# elements_v02.net
KiCad netlist of a schematic drawn in EAGLE
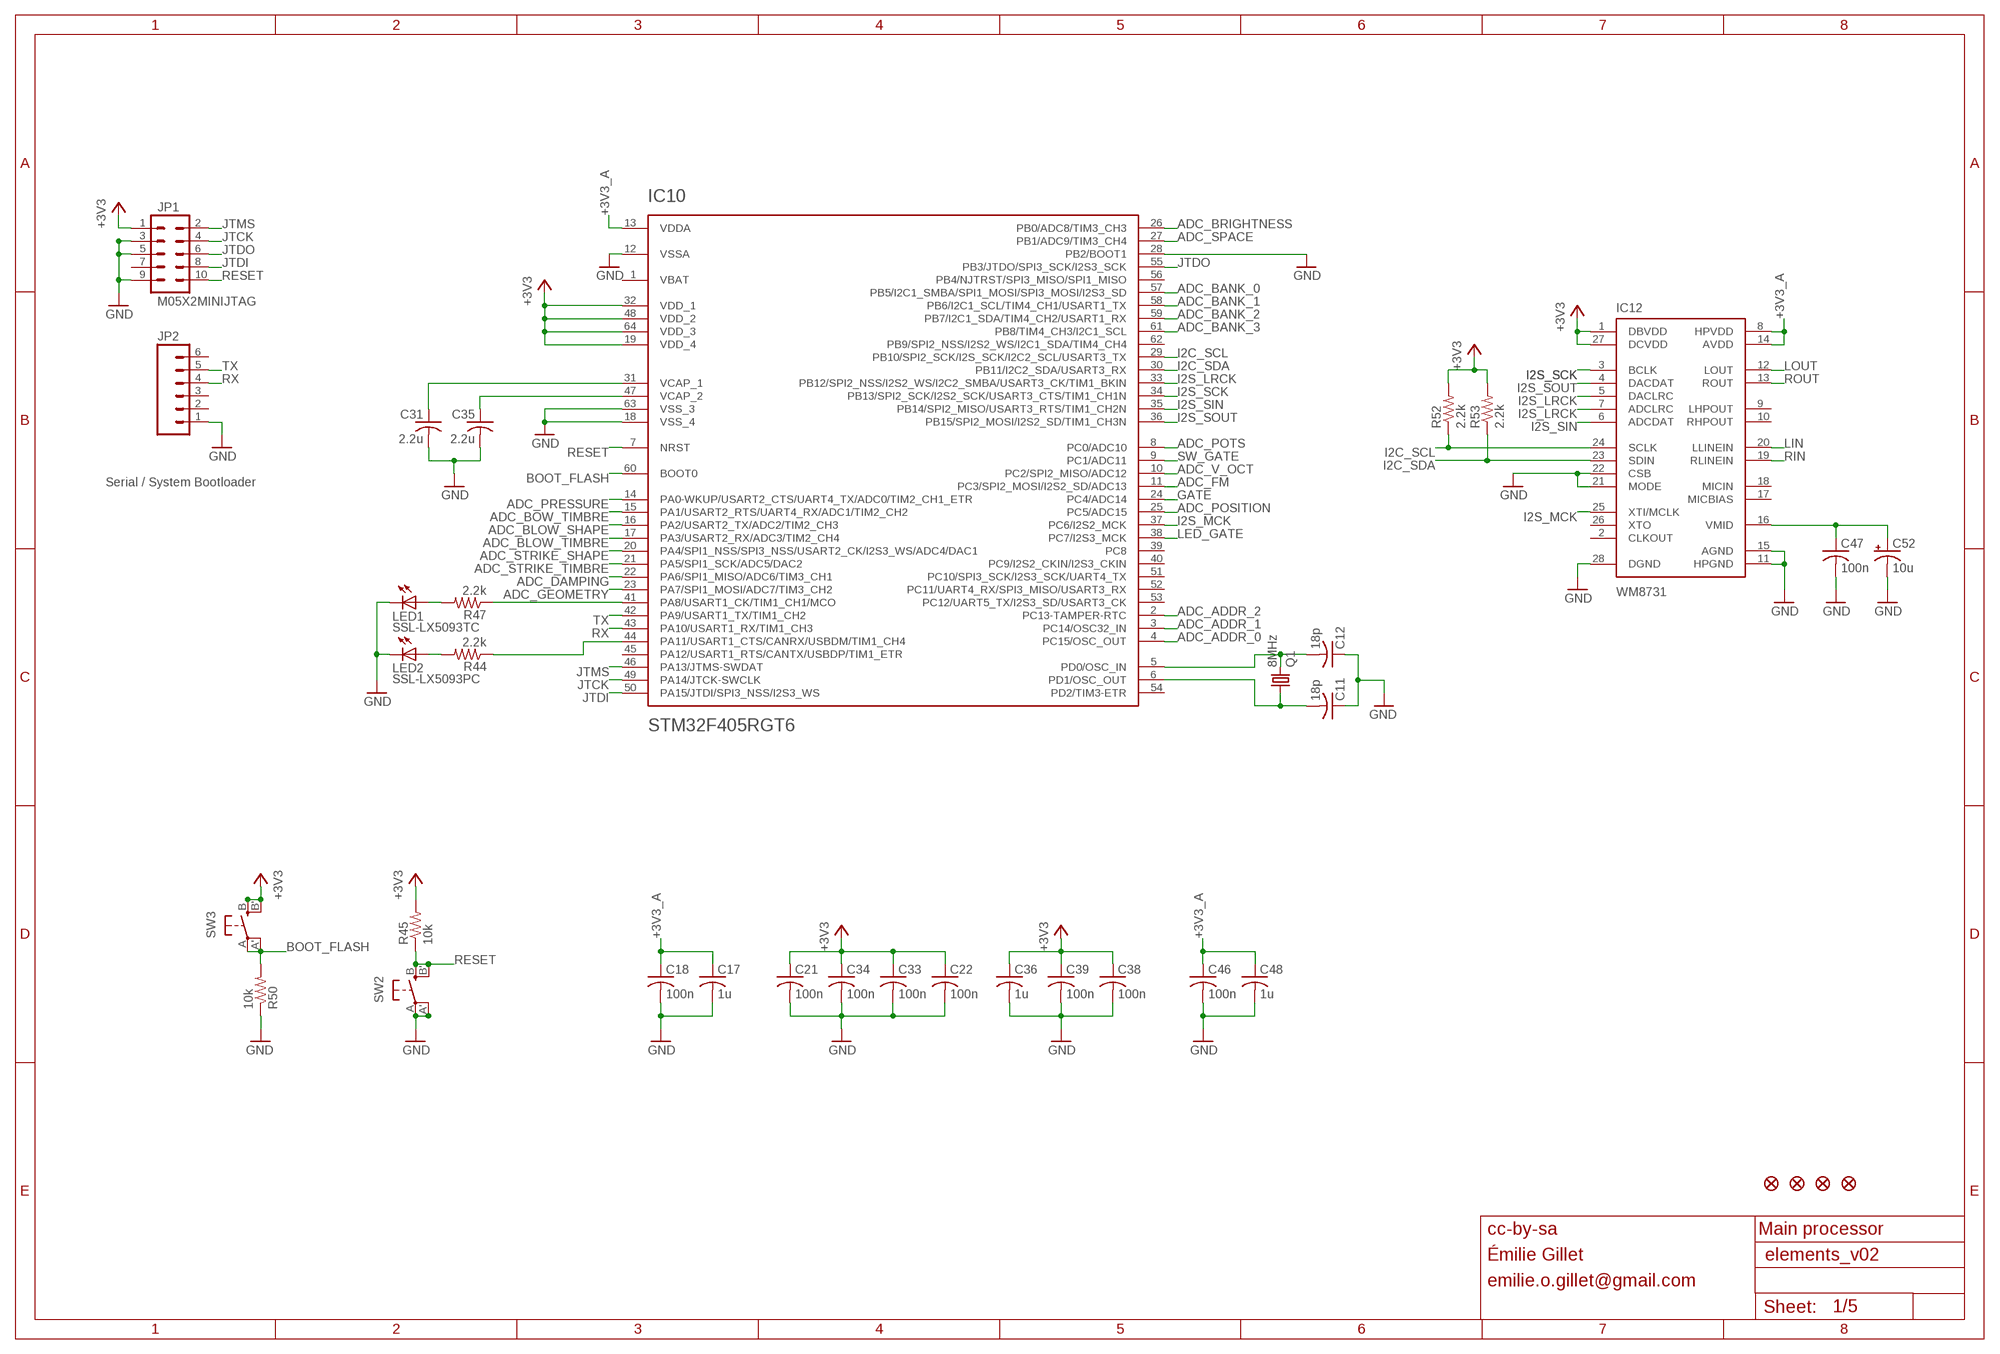
[diagram p0: schematic, sheet 1]
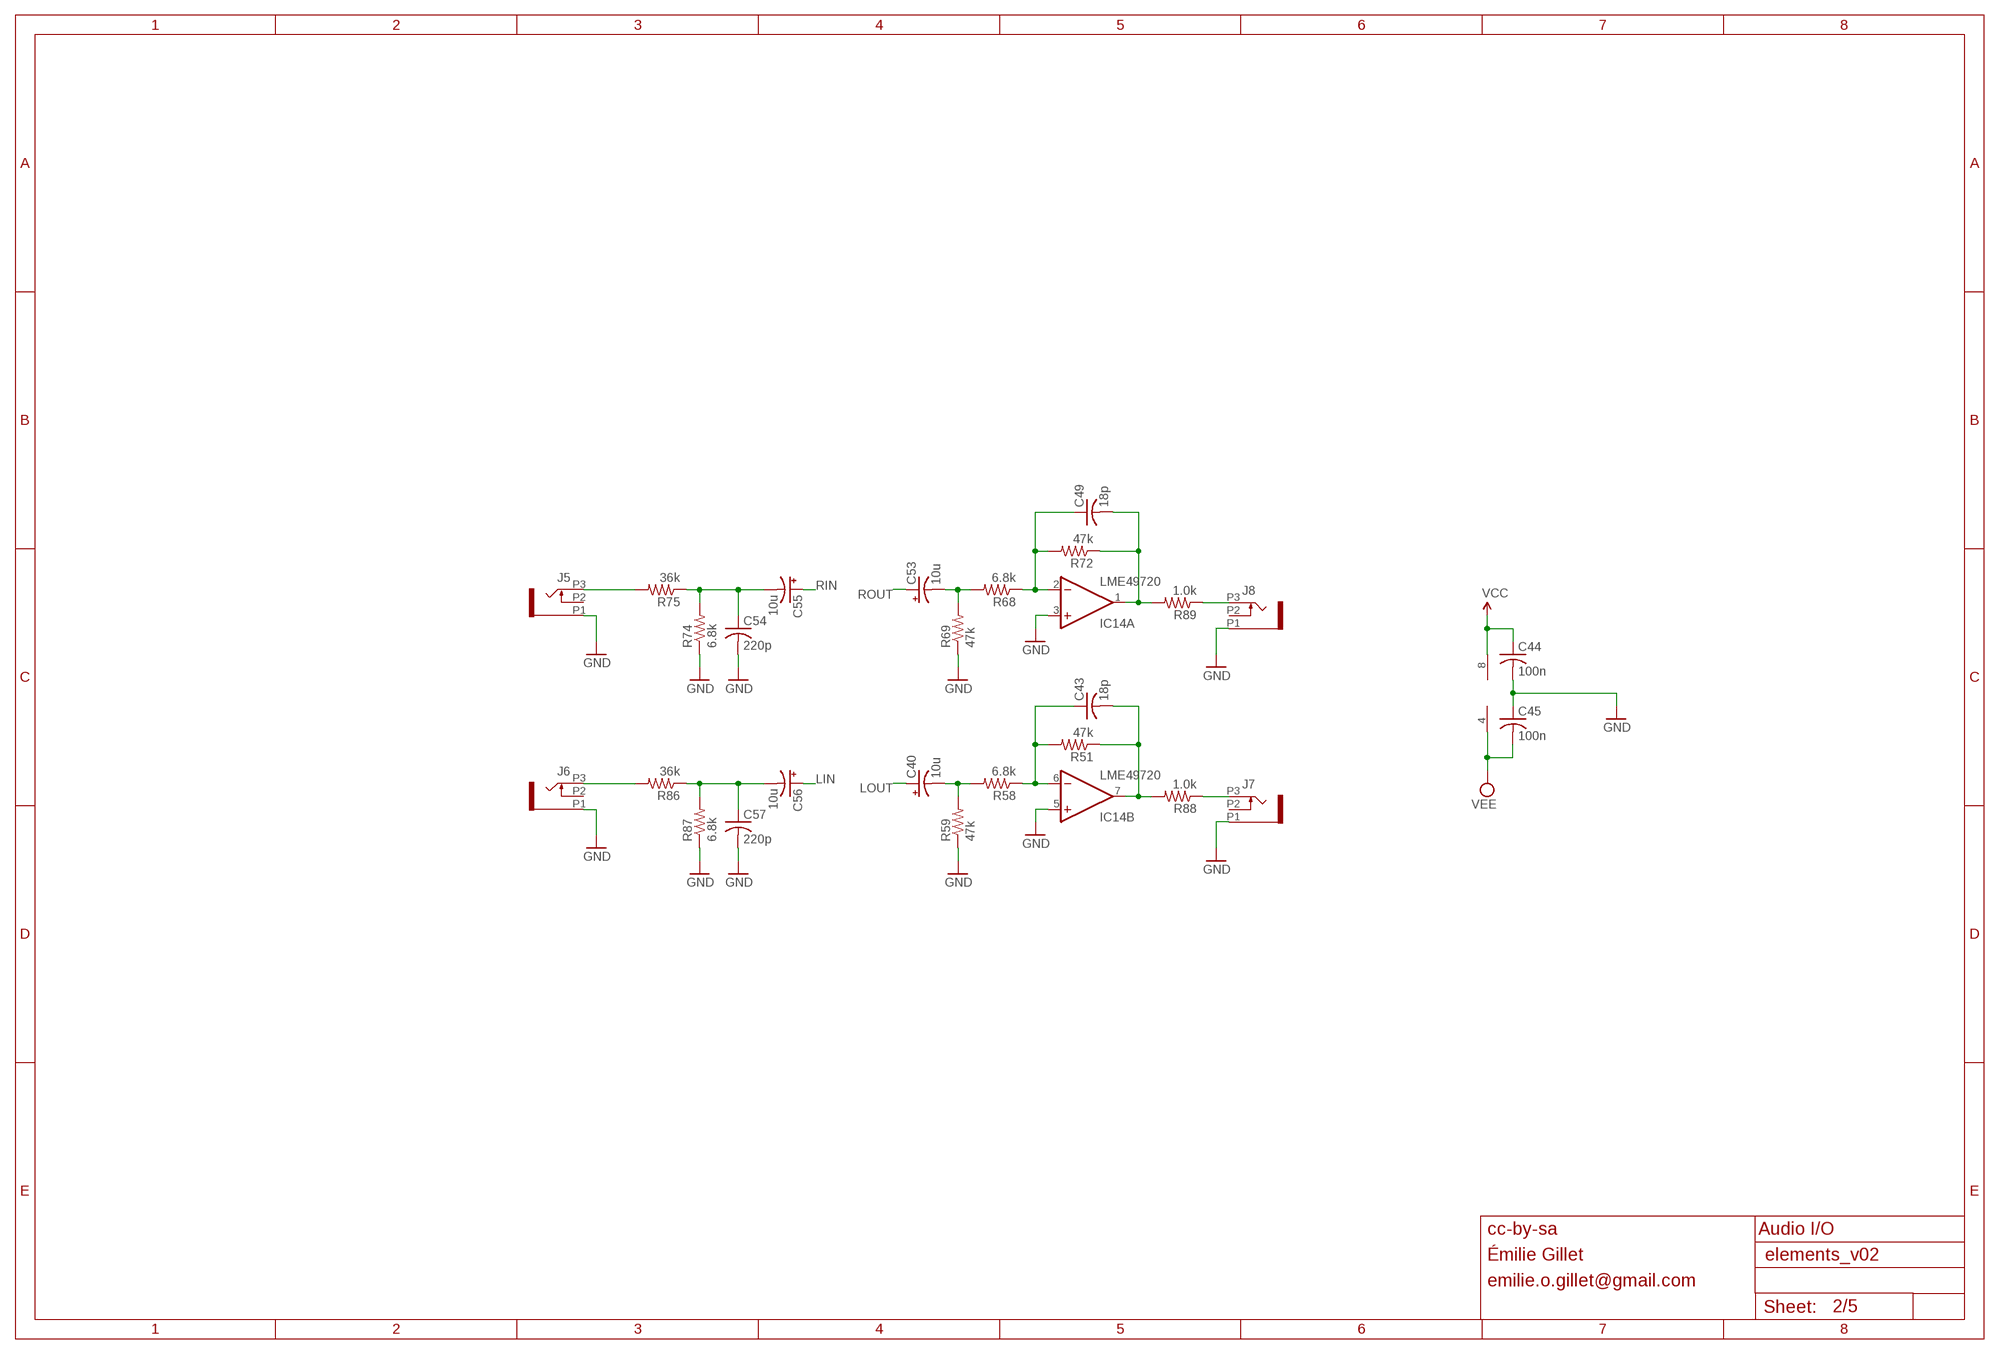
[diagram p1: schematic, sheet 2]
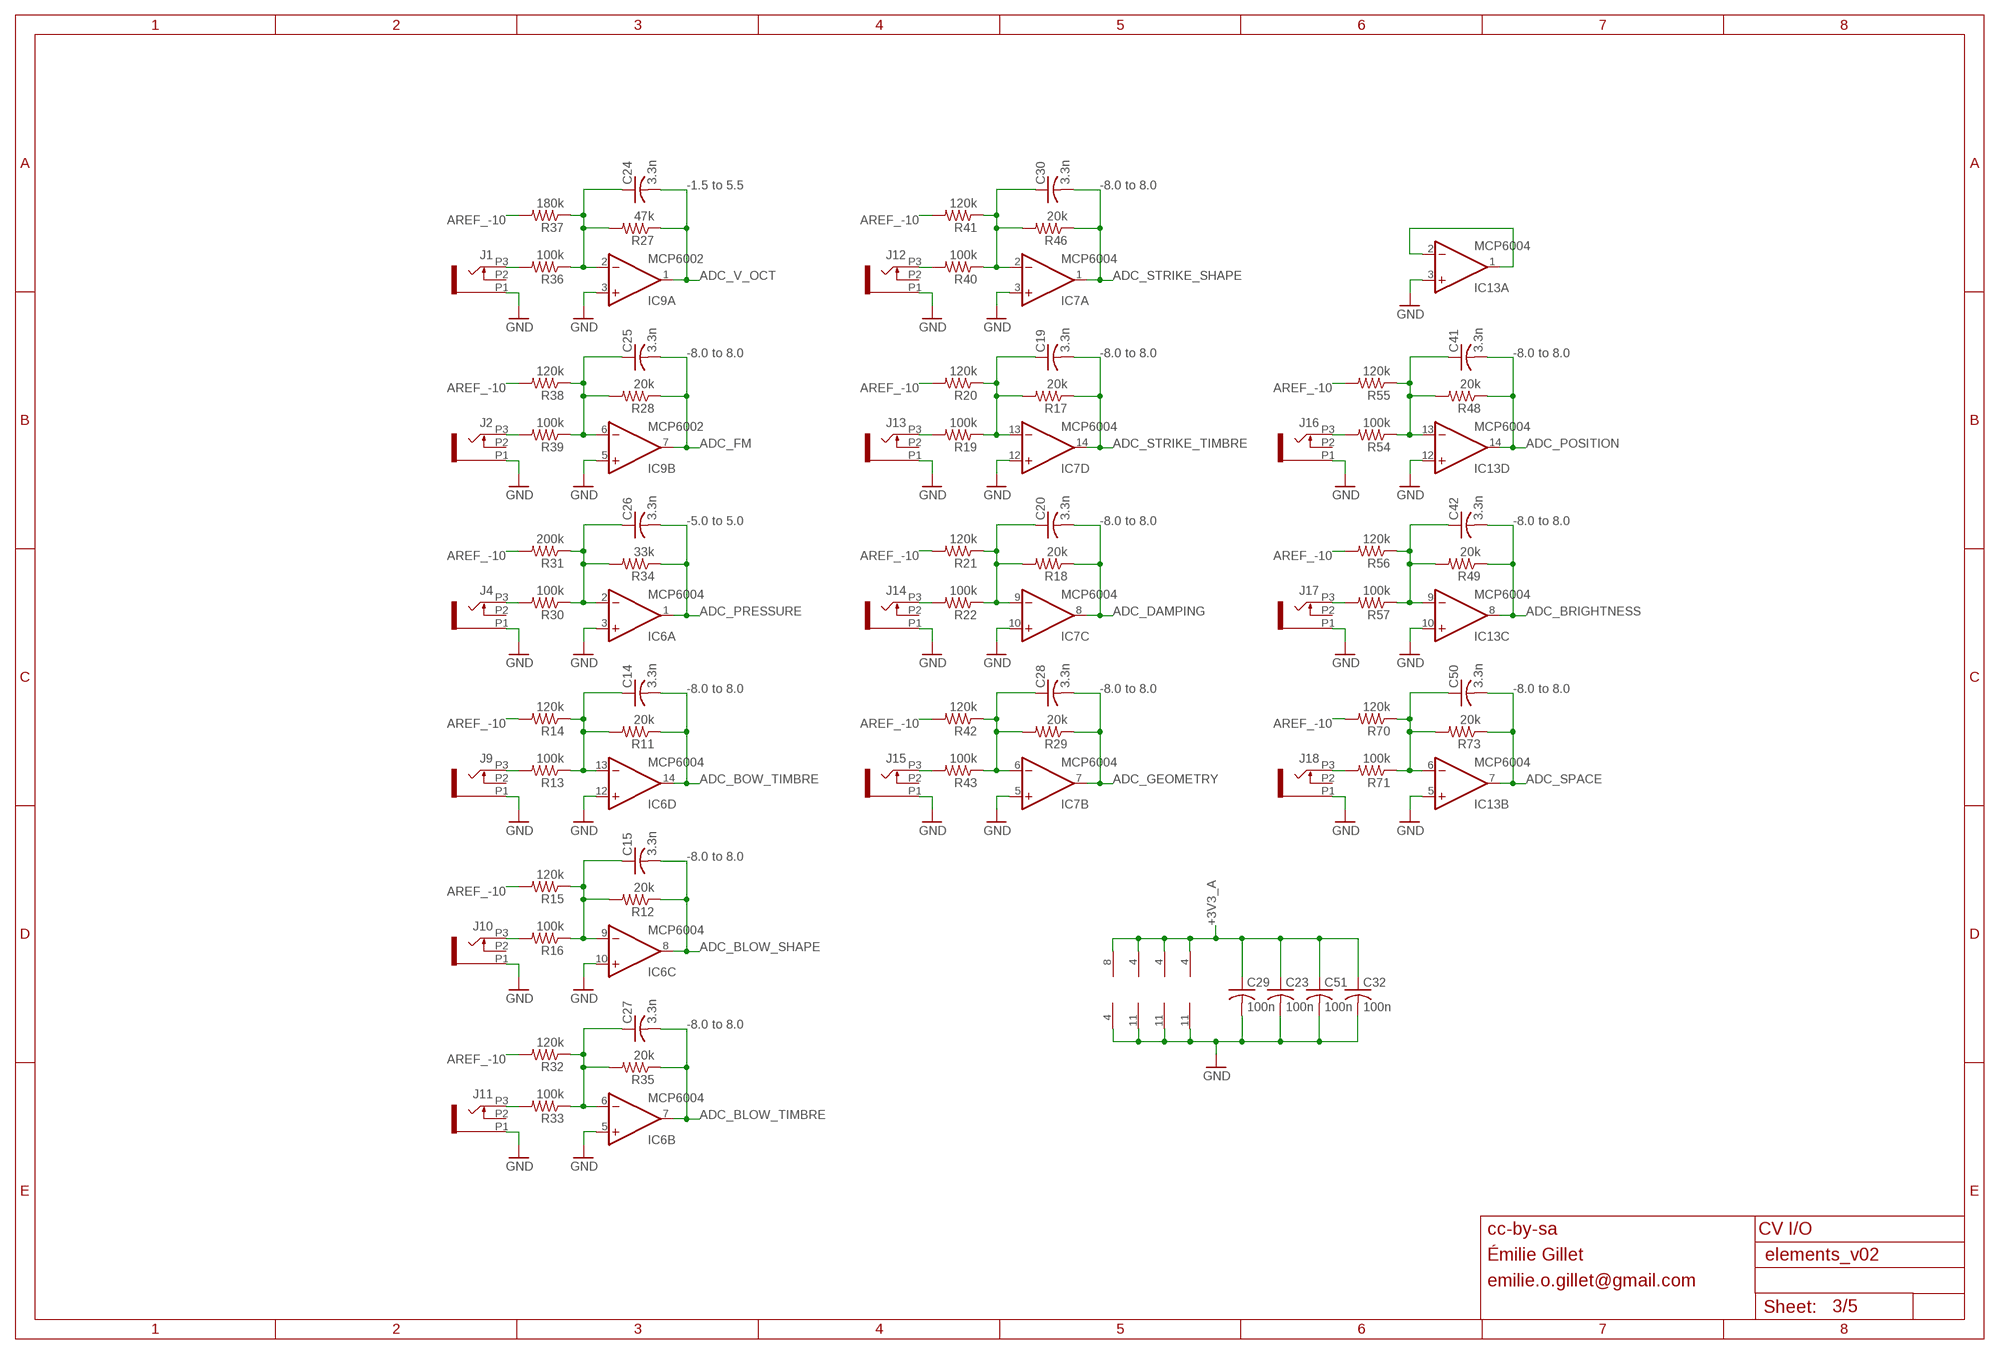
[diagram p2: schematic, sheet 3]
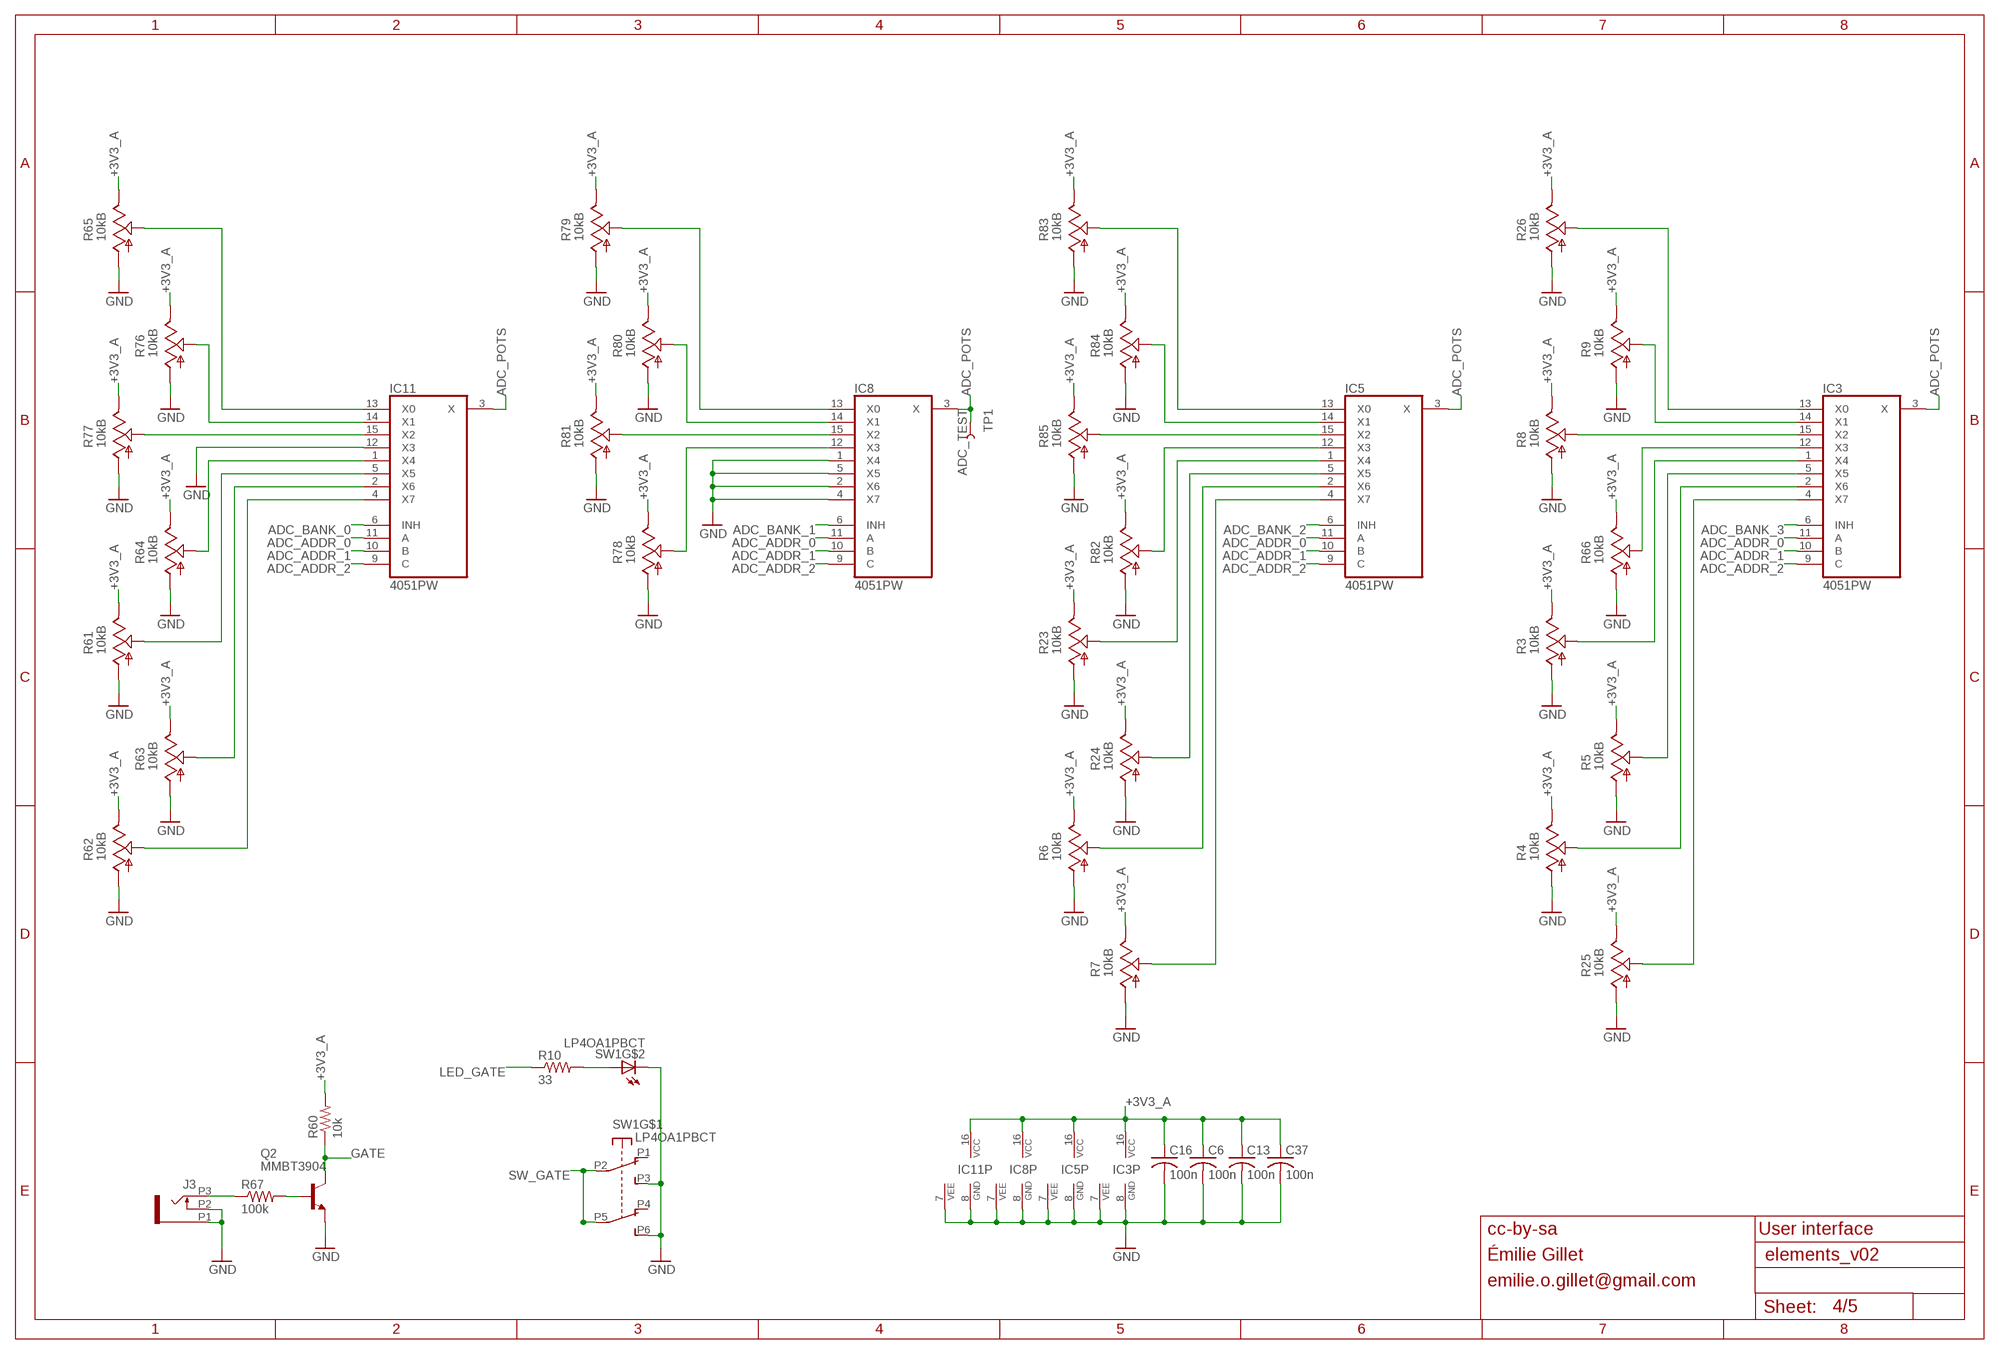
[diagram p3: schematic, sheet 4]
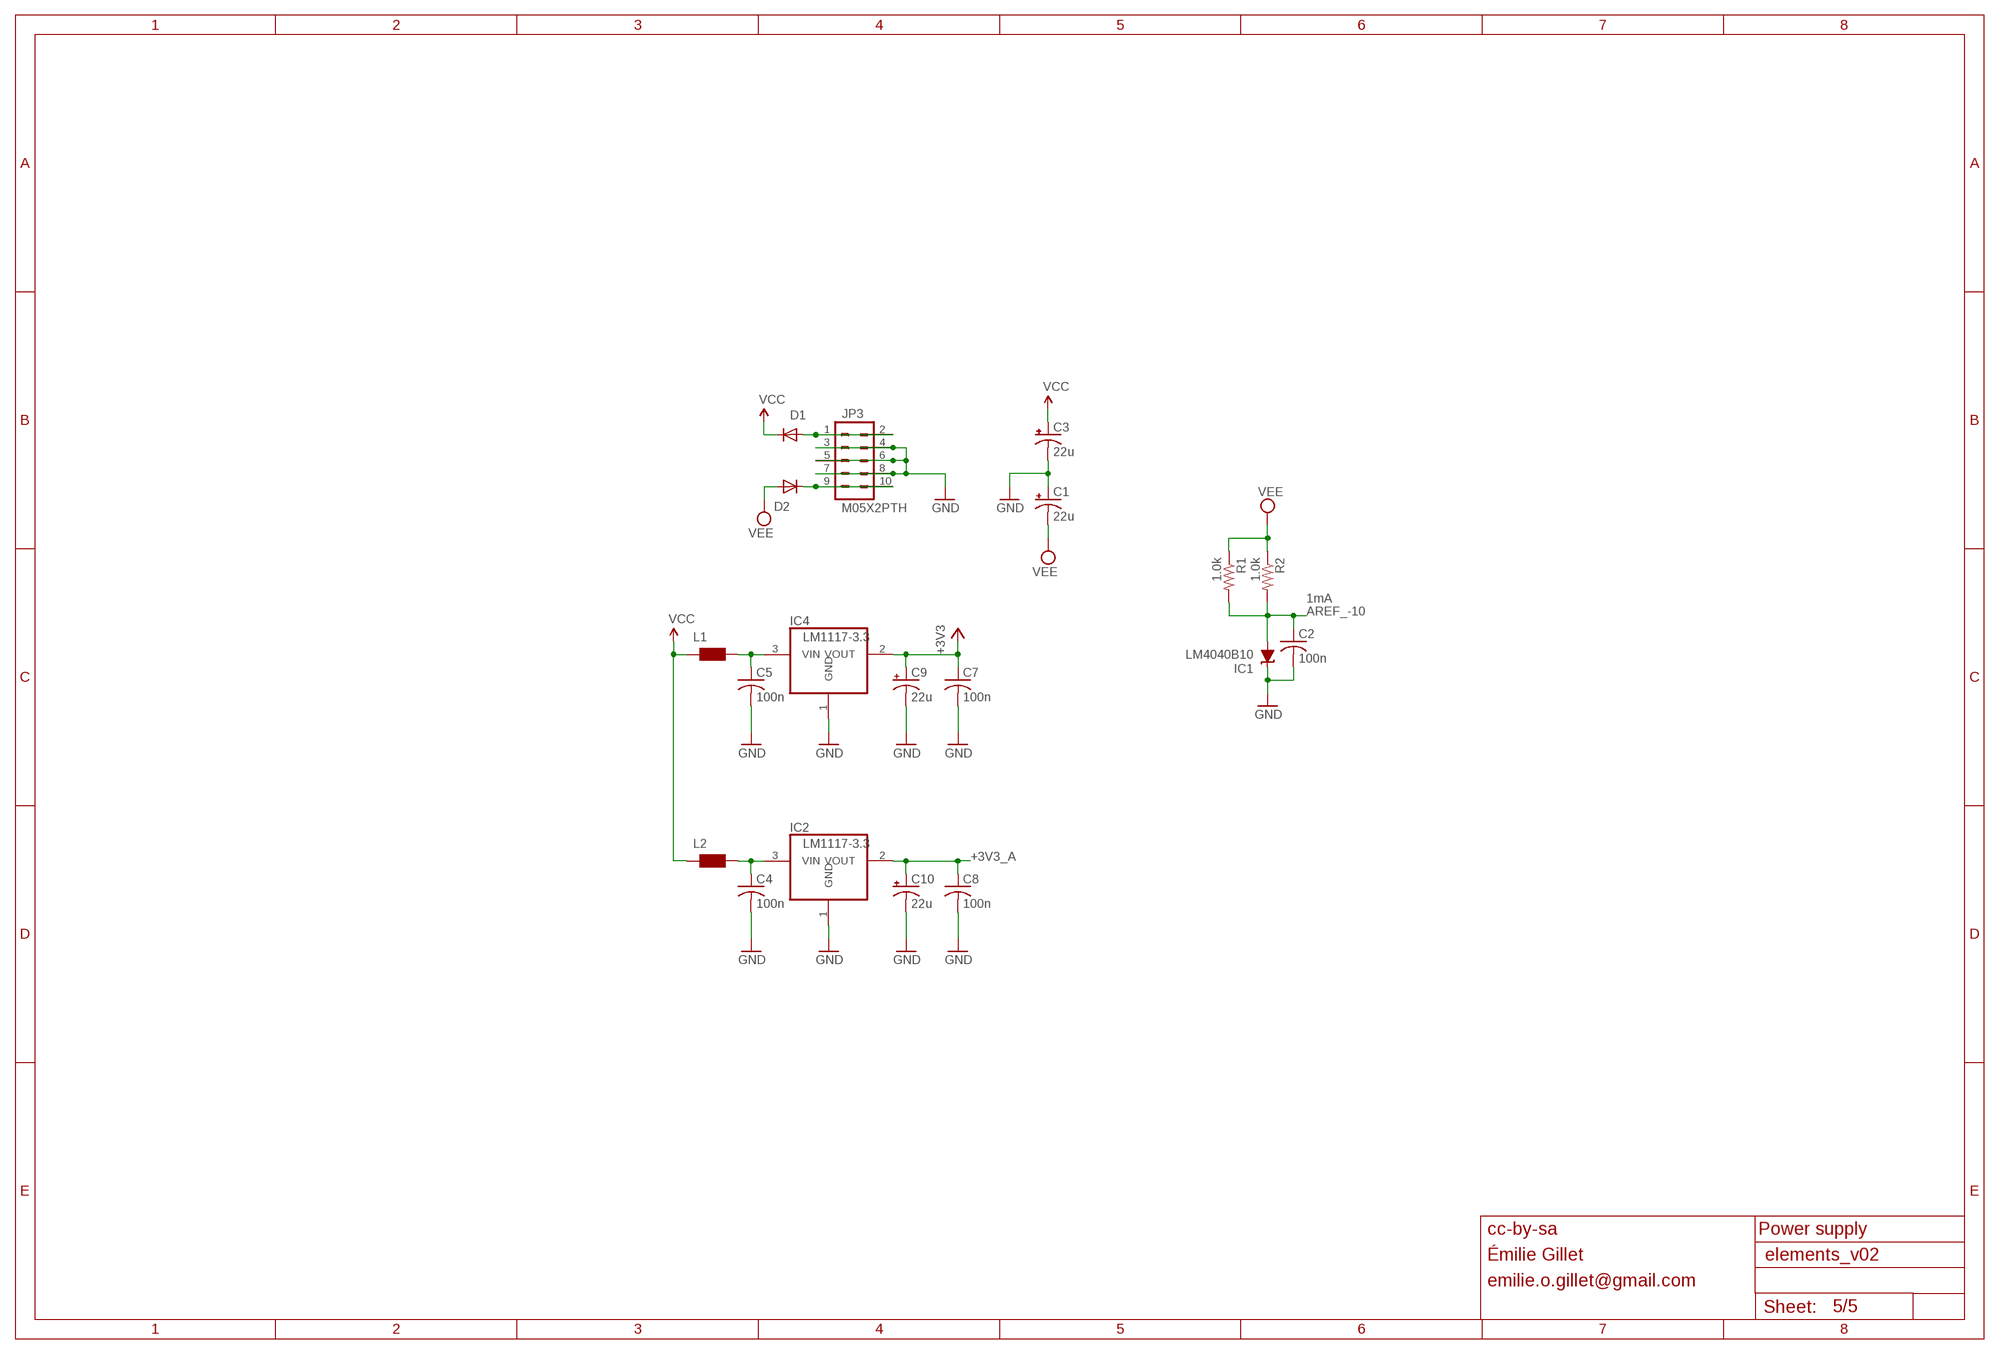
[diagram p4: schematic, sheet 5]

(export (version "E")
  (design (tool "Eeschema 10.0.6"))
  (components
    (comp (ref "C14")
      (value "3.3n")
      (footprint "eagle-import:C0603")
      (libsource (lib "eagle-import") (part "C-USC0603"))
    )
    (comp (ref "C15")
      (value "3.3n")
      (footprint "eagle-import:C0603")
      (libsource (lib "eagle-import") (part "C-USC0603"))
    )
    (comp (ref "C19")
      (value "3.3n")
      (footprint "eagle-import:C0603")
      (libsource (lib "eagle-import") (part "C-USC0603"))
    )
    (comp (ref "C20")
      (value "3.3n")
      (footprint "eagle-import:C0603")
      (libsource (lib "eagle-import") (part "C-USC0603"))
    )
    (comp (ref "C23")
      (value "100n")
      (footprint "eagle-import:C0603")
      (libsource (lib "eagle-import") (part "C-USC0603"))
    )
    (comp (ref "C24")
      (value "3.3n")
      (footprint "eagle-import:C0603")
      (libsource (lib "eagle-import") (part "C-USC0603"))
    )
    (comp (ref "C25")
      (value "3.3n")
      (footprint "eagle-import:C0603")
      (libsource (lib "eagle-import") (part "C-USC0603"))
    )
    (comp (ref "C26")
      (value "3.3n")
      (footprint "eagle-import:C0603")
      (libsource (lib "eagle-import") (part "C-USC0603"))
    )
    (comp (ref "C27")
      (value "3.3n")
      (footprint "eagle-import:C0603")
      (libsource (lib "eagle-import") (part "C-USC0603"))
    )
    (comp (ref "C28")
      (value "3.3n")
      (footprint "eagle-import:C0603")
      (libsource (lib "eagle-import") (part "C-USC0603"))
    )
    (comp (ref "C29")
      (value "100n")
      (footprint "eagle-import:C0603")
      (libsource (lib "eagle-import") (part "C-USC0603"))
    )
    (comp (ref "C30")
      (value "3.3n")
      (footprint "eagle-import:C0603")
      (libsource (lib "eagle-import") (part "C-USC0603"))
    )
    (comp (ref "C32")
      (value "100n")
      (footprint "eagle-import:C0603")
      (libsource (lib "eagle-import") (part "C-USC0603"))
    )
    (comp (ref "C41")
      (value "3.3n")
      (footprint "eagle-import:C0603")
      (libsource (lib "eagle-import") (part "C-USC0603"))
    )
    (comp (ref "C42")
      (value "3.3n")
      (footprint "eagle-import:C0603")
      (libsource (lib "eagle-import") (part "C-USC0603"))
    )
    (comp (ref "C50")
      (value "3.3n")
      (footprint "eagle-import:C0603")
      (libsource (lib "eagle-import") (part "C-USC0603"))
    )
    (comp (ref "C51")
      (value "100n")
      (footprint "eagle-import:C0603")
      (libsource (lib "eagle-import") (part "C-USC0603"))
    )
    (comp (ref "IC6")
      (value "MCP6004")
      (footprint "eagle-import:SO14")
      (libsource (lib "eagle-import") (part "TL074D"))
    )
    (comp (ref "IC7")
      (value "MCP6004")
      (footprint "eagle-import:SO14")
      (libsource (lib "eagle-import") (part "TL074D"))
    )
    (comp (ref "IC9")
      (value "MCP6002")
      (footprint "eagle-import:SO08")
      (libsource (lib "eagle-import") (part "TL072D"))
    )
    (comp (ref "IC13")
      (value "MCP6004")
      (footprint "eagle-import:SO14")
      (libsource (lib "eagle-import") (part "TL074D"))
    )
    (comp (ref "J1")
      (value "PJ301_THONKICONN6")
      (footprint "eagle-import:WQP_PJ_301M6")
      (libsource (lib "eagle-import") (part "PJ301_THONKICONN6"))
    )
    (comp (ref "J2")
      (value "PJ301_THONKICONN6")
      (footprint "eagle-import:WQP_PJ_301M6")
      (libsource (lib "eagle-import") (part "PJ301_THONKICONN6"))
    )
    (comp (ref "J4")
      (value "PJ301_THONKICONN6")
      (footprint "eagle-import:WQP_PJ_301M6")
      (libsource (lib "eagle-import") (part "PJ301_THONKICONN6"))
    )
    (comp (ref "J9")
      (value "PJ301_THONKICONN6")
      (footprint "eagle-import:WQP_PJ_301M6")
      (libsource (lib "eagle-import") (part "PJ301_THONKICONN6"))
    )
    (comp (ref "J10")
      (value "PJ301_THONKICONN6")
      (footprint "eagle-import:WQP_PJ_301M6")
      (libsource (lib "eagle-import") (part "PJ301_THONKICONN6"))
    )
    (comp (ref "J11")
      (value "PJ301_THONKICONN6")
      (footprint "eagle-import:WQP_PJ_301M6")
      (libsource (lib "eagle-import") (part "PJ301_THONKICONN6"))
    )
    (comp (ref "J12")
      (value "PJ301_THONKICONN6")
      (footprint "eagle-import:WQP_PJ_301M6")
      (libsource (lib "eagle-import") (part "PJ301_THONKICONN6"))
    )
    (comp (ref "J13")
      (value "PJ301_THONKICONN6")
      (footprint "eagle-import:WQP_PJ_301M6")
      (libsource (lib "eagle-import") (part "PJ301_THONKICONN6"))
    )
    (comp (ref "J14")
      (value "PJ301_THONKICONN6")
      (footprint "eagle-import:WQP_PJ_301M6")
      (libsource (lib "eagle-import") (part "PJ301_THONKICONN6"))
    )
    (comp (ref "J15")
      (value "PJ301_THONKICONN6")
      (footprint "eagle-import:WQP_PJ_301M6")
      (libsource (lib "eagle-import") (part "PJ301_THONKICONN6"))
    )
    (comp (ref "J16")
      (value "PJ301_THONKICONN6")
      (footprint "eagle-import:WQP_PJ_301M6")
      (libsource (lib "eagle-import") (part "PJ301_THONKICONN6"))
    )
    (comp (ref "J17")
      (value "PJ301_THONKICONN6")
      (footprint "eagle-import:WQP_PJ_301M6")
      (libsource (lib "eagle-import") (part "PJ301_THONKICONN6"))
    )
    (comp (ref "J18")
      (value "PJ301_THONKICONN6")
      (footprint "eagle-import:WQP_PJ_301M6")
      (libsource (lib "eagle-import") (part "PJ301_THONKICONN6"))
    )
    (comp (ref "R11")
      (value "20k")
      (footprint "eagle-import:R0603")
      (libsource (lib "eagle-import") (part "R-US_R0603"))
    )
    (comp (ref "R12")
      (value "20k")
      (footprint "eagle-import:R0603")
      (libsource (lib "eagle-import") (part "R-US_R0603"))
    )
    (comp (ref "R13")
      (value "100k")
      (footprint "eagle-import:R0603")
      (libsource (lib "eagle-import") (part "R-US_R0603"))
    )
    (comp (ref "R14")
      (value "120k")
      (footprint "eagle-import:R0603")
      (libsource (lib "eagle-import") (part "R-US_R0603"))
    )
    (comp (ref "R15")
      (value "120k")
      (footprint "eagle-import:R0603")
      (libsource (lib "eagle-import") (part "R-US_R0603"))
    )
    (comp (ref "R16")
      (value "100k")
      (footprint "eagle-import:R0603")
      (libsource (lib "eagle-import") (part "R-US_R0603"))
    )
    (comp (ref "R17")
      (value "20k")
      (footprint "eagle-import:R0603")
      (libsource (lib "eagle-import") (part "R-US_R0603"))
    )
    (comp (ref "R18")
      (value "20k")
      (footprint "eagle-import:R0603")
      (libsource (lib "eagle-import") (part "R-US_R0603"))
    )
    (comp (ref "R19")
      (value "100k")
      (footprint "eagle-import:R0603")
      (libsource (lib "eagle-import") (part "R-US_R0603"))
    )
    (comp (ref "R20")
      (value "120k")
      (footprint "eagle-import:R0603")
      (libsource (lib "eagle-import") (part "R-US_R0603"))
    )
    (comp (ref "R21")
      (value "120k")
      (footprint "eagle-import:R0603")
      (libsource (lib "eagle-import") (part "R-US_R0603"))
    )
    (comp (ref "R22")
      (value "100k")
      (footprint "eagle-import:R0603")
      (libsource (lib "eagle-import") (part "R-US_R0603"))
    )
    (comp (ref "R27")
      (value "47k")
      (footprint "eagle-import:R0603")
      (libsource (lib "eagle-import") (part "R-US_R0603"))
    )
    (comp (ref "R28")
      (value "20k")
      (footprint "eagle-import:R0603")
      (libsource (lib "eagle-import") (part "R-US_R0603"))
    )
    (comp (ref "R29")
      (value "20k")
      (footprint "eagle-import:R0603")
      (libsource (lib "eagle-import") (part "R-US_R0603"))
    )
    (comp (ref "R30")
      (value "100k")
      (footprint "eagle-import:R0603")
      (libsource (lib "eagle-import") (part "R-US_R0603"))
    )
    (comp (ref "R31")
      (value "200k")
      (footprint "eagle-import:R0603")
      (libsource (lib "eagle-import") (part "R-US_R0603"))
    )
    (comp (ref "R32")
      (value "120k")
      (footprint "eagle-import:R0603")
      (libsource (lib "eagle-import") (part "R-US_R0603"))
    )
    (comp (ref "R33")
      (value "100k")
      (footprint "eagle-import:R0603")
      (libsource (lib "eagle-import") (part "R-US_R0603"))
    )
    (comp (ref "R34")
      (value "33k")
      (footprint "eagle-import:R0603")
      (libsource (lib "eagle-import") (part "R-US_R0603"))
    )
    (comp (ref "R35")
      (value "20k")
      (footprint "eagle-import:R0603")
      (libsource (lib "eagle-import") (part "R-US_R0603"))
    )
    (comp (ref "R36")
      (value "100k")
      (footprint "eagle-import:R0603")
      (libsource (lib "eagle-import") (part "R-US_R0603"))
    )
    (comp (ref "R37")
      (value "180k")
      (footprint "eagle-import:R0603")
      (libsource (lib "eagle-import") (part "R-US_R0603"))
    )
    (comp (ref "R38")
      (value "120k")
      (footprint "eagle-import:R0603")
      (libsource (lib "eagle-import") (part "R-US_R0603"))
    )
    (comp (ref "R39")
      (value "100k")
      (footprint "eagle-import:R0603")
      (libsource (lib "eagle-import") (part "R-US_R0603"))
    )
    (comp (ref "R40")
      (value "100k")
      (footprint "eagle-import:R0603")
      (libsource (lib "eagle-import") (part "R-US_R0603"))
    )
    (comp (ref "R41")
      (value "120k")
      (footprint "eagle-import:R0603")
      (libsource (lib "eagle-import") (part "R-US_R0603"))
    )
    (comp (ref "R42")
      (value "120k")
      (footprint "eagle-import:R0603")
      (libsource (lib "eagle-import") (part "R-US_R0603"))
    )
    (comp (ref "R43")
      (value "100k")
      (footprint "eagle-import:R0603")
      (libsource (lib "eagle-import") (part "R-US_R0603"))
    )
    (comp (ref "R46")
      (value "20k")
      (footprint "eagle-import:R0603")
      (libsource (lib "eagle-import") (part "R-US_R0603"))
    )
    (comp (ref "R48")
      (value "20k")
      (footprint "eagle-import:R0603")
      (libsource (lib "eagle-import") (part "R-US_R0603"))
    )
    (comp (ref "R49")
      (value "20k")
      (footprint "eagle-import:R0603")
      (libsource (lib "eagle-import") (part "R-US_R0603"))
    )
    (comp (ref "R54")
      (value "100k")
      (footprint "eagle-import:R0603")
      (libsource (lib "eagle-import") (part "R-US_R0603"))
    )
    (comp (ref "R55")
      (value "120k")
      (footprint "eagle-import:R0603")
      (libsource (lib "eagle-import") (part "R-US_R0603"))
    )
    (comp (ref "R56")
      (value "120k")
      (footprint "eagle-import:R0603")
      (libsource (lib "eagle-import") (part "R-US_R0603"))
    )
    (comp (ref "R57")
      (value "100k")
      (footprint "eagle-import:R0603")
      (libsource (lib "eagle-import") (part "R-US_R0603"))
    )
    (comp (ref "R70")
      (value "120k")
      (footprint "eagle-import:R0603")
      (libsource (lib "eagle-import") (part "R-US_R0603"))
    )
    (comp (ref "R71")
      (value "100k")
      (footprint "eagle-import:R0603")
      (libsource (lib "eagle-import") (part "R-US_R0603"))
    )
    (comp (ref "R73")
      (value "20k")
      (footprint "eagle-import:R0603")
      (libsource (lib "eagle-import") (part "R-US_R0603"))
    )
    (comp (ref "C6")
      (value "100n")
      (footprint "eagle-import:C0603")
      (libsource (lib "eagle-import") (part "C-USC0603"))
    )
    (comp (ref "C13")
      (value "100n")
      (footprint "eagle-import:C0603")
      (libsource (lib "eagle-import") (part "C-USC0603"))
    )
    (comp (ref "C16")
      (value "100n")
      (footprint "eagle-import:C0603")
      (libsource (lib "eagle-import") (part "C-USC0603"))
    )
    (comp (ref "C37")
      (value "100n")
      (footprint "eagle-import:C0603")
      (libsource (lib "eagle-import") (part "C-USC0603"))
    )
    (comp (ref "IC3")
      (value "4051PW")
      (footprint "eagle-import:TSSOP16")
      (libsource (lib "eagle-import") (part "4051PW"))
    )
    (comp (ref "IC5")
      (value "4051PW")
      (footprint "eagle-import:TSSOP16")
      (libsource (lib "eagle-import") (part "4051PW"))
    )
    (comp (ref "IC8")
      (value "4051PW")
      (footprint "eagle-import:TSSOP16")
      (libsource (lib "eagle-import") (part "4051PW"))
    )
    (comp (ref "IC11")
      (value "4051PW")
      (footprint "eagle-import:TSSOP16")
      (libsource (lib "eagle-import") (part "4051PW"))
    )
    (comp (ref "J3")
      (value "PJ301_THONKICONN6")
      (footprint "eagle-import:WQP_PJ_301M6")
      (libsource (lib "eagle-import") (part "PJ301_THONKICONN6"))
    )
    (comp (ref "Q2")
      (value "MMBT3904")
      (footprint "eagle-import:SOT23-BEC")
      (libsource (lib "eagle-import") (part "-NPN-SOT23-BECMMBT3904LT1"))
    )
    (comp (ref "R3")
      (value "10kB")
      (footprint "eagle-import:ALPS_POT_VERTICAL_PS")
      (libsource (lib "eagle-import") (part "POT_USVERTICAL_PS"))
    )
    (comp (ref "R4")
      (value "10kB")
      (footprint "eagle-import:ALPS_POT_VERTICAL_PS")
      (libsource (lib "eagle-import") (part "POT_USVERTICAL_PS"))
    )
    (comp (ref "R5")
      (value "10kB")
      (footprint "eagle-import:ALPS_POT_VERTICAL_PS")
      (libsource (lib "eagle-import") (part "POT_USVERTICAL_PS"))
    )
    (comp (ref "R6")
      (value "10kB")
      (footprint "eagle-import:ALPS_POT_VERTICAL_PS")
      (libsource (lib "eagle-import") (part "POT_USVERTICAL_PS"))
    )
    (comp (ref "R7")
      (value "10kB")
      (footprint "eagle-import:ALPS_POT_VERTICAL_PS")
      (libsource (lib "eagle-import") (part "POT_USVERTICAL_PS"))
    )
    (comp (ref "R8")
      (value "10kB")
      (footprint "eagle-import:ALPS_POT_VERTICAL_PS")
      (libsource (lib "eagle-import") (part "POT_USVERTICAL_PS"))
    )
    (comp (ref "R9")
      (value "10kB")
      (footprint "eagle-import:ALPS_POT_VERTICAL_PS")
      (libsource (lib "eagle-import") (part "POT_USVERTICAL_PS"))
    )
    (comp (ref "R10")
      (value "33")
      (footprint "eagle-import:R0603")
      (libsource (lib "eagle-import") (part "R-US_R0603"))
    )
    (comp (ref "R23")
      (value "10kB")
      (footprint "eagle-import:ALPS_POT_VERTICAL_PS")
      (libsource (lib "eagle-import") (part "POT_USVERTICAL_PS"))
    )
    (comp (ref "R24")
      (value "10kB")
      (footprint "eagle-import:ALPS_POT_VERTICAL_PS")
      (libsource (lib "eagle-import") (part "POT_USVERTICAL_PS"))
    )
    (comp (ref "R25")
      (value "10kB")
      (footprint "eagle-import:ALPS_POT_VERTICAL_PS")
      (libsource (lib "eagle-import") (part "POT_USVERTICAL_PS"))
    )
    (comp (ref "R26")
      (value "10kB")
      (footprint "eagle-import:ALPS_POT_VERTICAL_PS")
      (libsource (lib "eagle-import") (part "POT_USVERTICAL_PS"))
    )
    (comp (ref "R60")
      (value "10k")
      (footprint "eagle-import:R0603")
      (libsource (lib "eagle-import") (part "R-US_R0603"))
    )
    (comp (ref "R61")
      (value "10kB")
      (footprint "eagle-import:ALPS_POT_VERTICAL_PS")
      (libsource (lib "eagle-import") (part "POT_USVERTICAL_PS"))
    )
    (comp (ref "R62")
      (value "10kB")
      (footprint "eagle-import:ALPS_POT_VERTICAL_PS")
      (libsource (lib "eagle-import") (part "POT_USVERTICAL_PS"))
    )
    (comp (ref "R63")
      (value "10kB")
      (footprint "eagle-import:ALPS_POT_VERTICAL_PS")
      (libsource (lib "eagle-import") (part "POT_USVERTICAL_PS"))
    )
    (comp (ref "R64")
      (value "10kB")
      (footprint "eagle-import:ALPS_POT_VERTICAL_PS")
      (libsource (lib "eagle-import") (part "POT_USVERTICAL_PS"))
    )
    (comp (ref "R65")
      (value "10kB")
      (footprint "eagle-import:ALPS_POT_VERTICAL_PS")
      (libsource (lib "eagle-import") (part "POT_USVERTICAL_PS"))
    )
    (comp (ref "R66")
      (value "10kB")
      (footprint "eagle-import:ALPS_POT_VERTICAL_PS")
      (libsource (lib "eagle-import") (part "POT_USVERTICAL_PS"))
    )
    (comp (ref "R67")
      (value "100k")
      (footprint "eagle-import:R0603")
      (libsource (lib "eagle-import") (part "R-US_R0603"))
    )
    (comp (ref "R76")
      (value "10kB")
      (footprint "eagle-import:ALPS_POT_VERTICAL")
      (libsource (lib "eagle-import") (part "POT_USVERTICAL"))
    )
    (comp (ref "R77")
      (value "10kB")
      (footprint "eagle-import:ALPS_POT_VERTICAL")
      (libsource (lib "eagle-import") (part "POT_USVERTICAL"))
    )
    (comp (ref "R78")
      (value "10kB")
      (footprint "eagle-import:ALPS_POT_VERTICAL")
      (libsource (lib "eagle-import") (part "POT_USVERTICAL"))
    )
    (comp (ref "R79")
      (value "10kB")
      (footprint "eagle-import:ALPS_POT_VERTICAL")
      (libsource (lib "eagle-import") (part "POT_USVERTICAL"))
    )
    (comp (ref "R80")
      (value "10kB")
      (footprint "eagle-import:ALPS_POT_VERTICAL")
      (libsource (lib "eagle-import") (part "POT_USVERTICAL"))
    )
    (comp (ref "R81")
      (value "10kB")
      (footprint "eagle-import:ALPS_POT_VERTICAL")
      (libsource (lib "eagle-import") (part "POT_USVERTICAL"))
    )
    (comp (ref "R82")
      (value "10kB")
      (footprint "eagle-import:ALPS_POT_VERTICAL")
      (libsource (lib "eagle-import") (part "POT_USVERTICAL"))
    )
    (comp (ref "R83")
      (value "10kB")
      (footprint "eagle-import:ALPS_POT_VERTICAL")
      (libsource (lib "eagle-import") (part "POT_USVERTICAL"))
    )
    (comp (ref "R84")
      (value "10kB")
      (footprint "eagle-import:ALPS_POT_VERTICAL")
      (libsource (lib "eagle-import") (part "POT_USVERTICAL"))
    )
    (comp (ref "R85")
      (value "10kB")
      (footprint "eagle-import:ALPS_POT_VERTICAL")
      (libsource (lib "eagle-import") (part "POT_USVERTICAL"))
    )
    (comp (ref "SW1")
      (value "LP4OA1PBCT")
      (footprint "eagle-import:LP4OA1PBCT")
      (libsource (lib "eagle-import") (part "LP4OA1PBCT"))
    )
    (comp (ref "TP1")
      (value "ADC_TEST")
      (footprint "eagle-import:PAD.03X.03")
      (libsource (lib "eagle-import") (part "TEST-POINT3"))
    )
    (comp (ref "C40")
      (value "10u")
      (footprint "eagle-import:PANASONIC_B")
      (libsource (lib "eagle-import") (part "CPOL-USB"))
    )
    (comp (ref "C43")
      (value "18p")
      (footprint "eagle-import:C0603")
      (libsource (lib "eagle-import") (part "C-USC0603"))
    )
    (comp (ref "C44")
      (value "100n")
      (footprint "eagle-import:C0603")
      (libsource (lib "eagle-import") (part "C-USC0603"))
    )
    (comp (ref "C45")
      (value "100n")
      (footprint "eagle-import:C0603")
      (libsource (lib "eagle-import") (part "C-USC0603"))
    )
    (comp (ref "C49")
      (value "18p")
      (footprint "eagle-import:C0603")
      (libsource (lib "eagle-import") (part "C-USC0603"))
    )
    (comp (ref "C53")
      (value "10u")
      (footprint "eagle-import:PANASONIC_B")
      (libsource (lib "eagle-import") (part "CPOL-USB"))
    )
    (comp (ref "C54")
      (value "220p")
      (footprint "eagle-import:C0603")
      (libsource (lib "eagle-import") (part "C-USC0603"))
    )
    (comp (ref "C55")
      (value "10u")
      (footprint "eagle-import:PANASONIC_B")
      (libsource (lib "eagle-import") (part "CPOL-USB"))
    )
    (comp (ref "C56")
      (value "10u")
      (footprint "eagle-import:PANASONIC_B")
      (libsource (lib "eagle-import") (part "CPOL-USB"))
    )
    (comp (ref "C57")
      (value "220p")
      (footprint "eagle-import:C0603")
      (libsource (lib "eagle-import") (part "C-USC0603"))
    )
    (comp (ref "IC14")
      (value "LME49720")
      (footprint "eagle-import:SO08")
      (libsource (lib "eagle-import") (part "og-linear_TL072D"))
    )
    (comp (ref "J5")
      (value "PJ301_THONKICONN6")
      (footprint "eagle-import:WQP_PJ_301M6")
      (libsource (lib "eagle-import") (part "PJ301_THONKICONN6"))
    )
    (comp (ref "J6")
      (value "PJ301_THONKICONN6")
      (footprint "eagle-import:WQP_PJ_301M6")
      (libsource (lib "eagle-import") (part "PJ301_THONKICONN6"))
    )
    (comp (ref "J7")
      (value "PJ301_THONKICONN6")
      (footprint "eagle-import:WQP_PJ_301M6")
      (libsource (lib "eagle-import") (part "PJ301_THONKICONN6"))
    )
    (comp (ref "J8")
      (value "PJ301_THONKICONN6")
      (footprint "eagle-import:WQP_PJ_301M6")
      (libsource (lib "eagle-import") (part "PJ301_THONKICONN6"))
    )
    (comp (ref "R51")
      (value "47k")
      (footprint "eagle-import:R0603")
      (libsource (lib "eagle-import") (part "R-US_R0603"))
    )
    (comp (ref "R58")
      (value "6.8k")
      (footprint "eagle-import:R0603")
      (libsource (lib "eagle-import") (part "R-US_R0603"))
    )
    (comp (ref "R59")
      (value "47k")
      (footprint "eagle-import:R0603")
      (libsource (lib "eagle-import") (part "R-US_R0603"))
    )
    (comp (ref "R68")
      (value "6.8k")
      (footprint "eagle-import:R0603")
      (libsource (lib "eagle-import") (part "R-US_R0603"))
    )
    (comp (ref "R69")
      (value "47k")
      (footprint "eagle-import:R0603")
      (libsource (lib "eagle-import") (part "R-US_R0603"))
    )
    (comp (ref "R72")
      (value "47k")
      (footprint "eagle-import:R0603")
      (libsource (lib "eagle-import") (part "R-US_R0603"))
    )
    (comp (ref "R74")
      (value "6.8k")
      (footprint "eagle-import:R0603")
      (libsource (lib "eagle-import") (part "R-US_R0603"))
    )
    (comp (ref "R75")
      (value "36k")
      (footprint "eagle-import:R0603")
      (libsource (lib "eagle-import") (part "R-US_R0603"))
    )
    (comp (ref "R86")
      (value "36k")
      (footprint "eagle-import:R0603")
      (libsource (lib "eagle-import") (part "R-US_R0603"))
    )
    (comp (ref "R87")
      (value "6.8k")
      (footprint "eagle-import:R0603")
      (libsource (lib "eagle-import") (part "R-US_R0603"))
    )
    (comp (ref "R88")
      (value "1.0k")
      (footprint "eagle-import:R0603")
      (libsource (lib "eagle-import") (part "R-US_R0603"))
    )
    (comp (ref "R89")
      (value "1.0k")
      (footprint "eagle-import:R0603")
      (libsource (lib "eagle-import") (part "R-US_R0603"))
    )
    (comp (ref "C11")
      (value "18p")
      (footprint "eagle-import:C0603")
      (libsource (lib "eagle-import") (part "C-USC0603"))
    )
    (comp (ref "C12")
      (value "18p")
      (footprint "eagle-import:C0603")
      (libsource (lib "eagle-import") (part "C-USC0603"))
    )
    (comp (ref "C17")
      (value "1u")
      (footprint "eagle-import:C0603")
      (libsource (lib "eagle-import") (part "C-USC0603"))
    )
    (comp (ref "C18")
      (value "100n")
      (footprint "eagle-import:C0603")
      (libsource (lib "eagle-import") (part "C-USC0603"))
    )
    (comp (ref "C21")
      (value "100n")
      (footprint "eagle-import:C0603")
      (libsource (lib "eagle-import") (part "C-USC0603"))
    )
    (comp (ref "C22")
      (value "100n")
      (footprint "eagle-import:C0603")
      (libsource (lib "eagle-import") (part "C-USC0603"))
    )
    (comp (ref "C31")
      (value "2.2u")
      (footprint "eagle-import:C0805")
      (libsource (lib "eagle-import") (part "C-USC0805"))
    )
    (comp (ref "C33")
      (value "100n")
      (footprint "eagle-import:C0603")
      (libsource (lib "eagle-import") (part "C-USC0603"))
    )
    (comp (ref "C34")
      (value "100n")
      (footprint "eagle-import:C0603")
      (libsource (lib "eagle-import") (part "C-USC0603"))
    )
    (comp (ref "C35")
      (value "2.2u")
      (footprint "eagle-import:C0805")
      (libsource (lib "eagle-import") (part "C-USC0805"))
    )
    (comp (ref "C36")
      (value "1u")
      (footprint "eagle-import:C0603")
      (libsource (lib "eagle-import") (part "C-USC0603"))
    )
    (comp (ref "C38")
      (value "100n")
      (footprint "eagle-import:C0603")
      (libsource (lib "eagle-import") (part "C-USC0603"))
    )
    (comp (ref "C39")
      (value "100n")
      (footprint "eagle-import:C0603")
      (libsource (lib "eagle-import") (part "C-USC0603"))
    )
    (comp (ref "C46")
      (value "100n")
      (footprint "eagle-import:C0603")
      (libsource (lib "eagle-import") (part "C-USC0603"))
    )
    (comp (ref "C47")
      (value "100n")
      (footprint "eagle-import:C0603")
      (libsource (lib "eagle-import") (part "C-USC0603"))
    )
    (comp (ref "C48")
      (value "1u")
      (footprint "eagle-import:C0603")
      (libsource (lib "eagle-import") (part "C-USC0603"))
    )
    (comp (ref "C52")
      (value "10u")
      (footprint "eagle-import:PANASONIC_B")
      (libsource (lib "eagle-import") (part "CPOL-USB"))
    )
    (comp (ref "F1")
      (value "FIDUCIAL1X2")
      (footprint "eagle-import:FIDUCIAL-1X2")
      (libsource (lib "eagle-import") (part "FIDUCIAL1X2"))
    )
    (comp (ref "F2")
      (value "FIDUCIAL1X2")
      (footprint "eagle-import:FIDUCIAL-1X2")
      (libsource (lib "eagle-import") (part "FIDUCIAL1X2"))
    )
    (comp (ref "F3")
      (value "FIDUCIAL1X2")
      (footprint "eagle-import:FIDUCIAL-1X2")
      (libsource (lib "eagle-import") (part "FIDUCIAL1X2"))
    )
    (comp (ref "F4")
      (value "FIDUCIAL1X2")
      (footprint "eagle-import:FIDUCIAL-1X2")
      (libsource (lib "eagle-import") (part "FIDUCIAL1X2"))
    )
    (comp (ref "IC10")
      (value "STM32F405RGT6")
      (footprint "eagle-import:TQFP-10X10-64")
      (libsource (lib "eagle-import") (part "STM32F20X"))
    )
    (comp (ref "IC12")
      (value "WM8731")
      (footprint "eagle-import:SSOP28")
      (libsource (lib "eagle-import") (part "WM8731"))
    )
    (comp (ref "JP1")
      (value "M05X2MINIJTAG")
      (footprint "eagle-import:2X5-1.27")
      (libsource (lib "eagle-import") (part "M05X2MINIJTAG"))
    )
    (comp (ref "JP2")
      (value "M06SIP")
      (footprint "eagle-import:1X06")
      (libsource (lib "eagle-import") (part "M06SIP"))
    )
    (comp (ref "LED1")
      (value "SSL-LX5093TC")
      (footprint "eagle-import:LED5MM")
      (libsource (lib "eagle-import") (part "LED5MM"))
    )
    (comp (ref "LED2")
      (value "SSL-LX5093PC")
      (footprint "eagle-import:LED5MM")
      (libsource (lib "eagle-import") (part "LED5MM"))
    )
    (comp (ref "Q1")
      (value "8MHz")
      (footprint "eagle-import:HC49UP")
      (libsource (lib "eagle-import") (part "CRYSTALHC49UP"))
    )
    (comp (ref "R44")
      (value "2.2k")
      (footprint "eagle-import:R0603")
      (libsource (lib "eagle-import") (part "R-US_R0603"))
    )
    (comp (ref "R45")
      (value "10k")
      (footprint "eagle-import:R0603")
      (libsource (lib "eagle-import") (part "R-US_R0603"))
    )
    (comp (ref "R47")
      (value "2.2k")
      (footprint "eagle-import:R0603")
      (libsource (lib "eagle-import") (part "R-US_R0603"))
    )
    (comp (ref "R50")
      (value "10k")
      (footprint "eagle-import:R0603")
      (libsource (lib "eagle-import") (part "R-US_R0603"))
    )
    (comp (ref "R52")
      (value "2.2k")
      (footprint "eagle-import:R0603")
      (libsource (lib "eagle-import") (part "R-US_R0603"))
    )
    (comp (ref "R53")
      (value "2.2k")
      (footprint "eagle-import:R0603")
      (libsource (lib "eagle-import") (part "R-US_R0603"))
    )
    (comp (ref "SW2")
      (value "EVQQ2")
      (footprint "eagle-import:EVQ-Q2")
      (libsource (lib "eagle-import") (part "EVQQ2"))
    )
    (comp (ref "SW3")
      (value "EVQQ2")
      (footprint "eagle-import:EVQ-Q2")
      (libsource (lib "eagle-import") (part "EVQQ2"))
    )
    (comp (ref "C1")
      (value "22u")
      (footprint "eagle-import:PANASONIC_C")
      (libsource (lib "eagle-import") (part "CPOL-USC"))
    )
    (comp (ref "C2")
      (value "100n")
      (footprint "eagle-import:C0603")
      (libsource (lib "eagle-import") (part "C-USC0603"))
    )
    (comp (ref "C3")
      (value "22u")
      (footprint "eagle-import:PANASONIC_C")
      (libsource (lib "eagle-import") (part "CPOL-USC"))
    )
    (comp (ref "C4")
      (value "100n")
      (footprint "eagle-import:C0603")
      (libsource (lib "eagle-import") (part "C-USC0603"))
    )
    (comp (ref "C5")
      (value "100n")
      (footprint "eagle-import:C0603")
      (libsource (lib "eagle-import") (part "C-USC0603"))
    )
    (comp (ref "C7")
      (value "100n")
      (footprint "eagle-import:C0603")
      (libsource (lib "eagle-import") (part "C-USC0603"))
    )
    (comp (ref "C8")
      (value "100n")
      (footprint "eagle-import:C0603")
      (libsource (lib "eagle-import") (part "C-USC0603"))
    )
    (comp (ref "C9")
      (value "22u")
      (footprint "eagle-import:PANASONIC_C")
      (libsource (lib "eagle-import") (part "CPOL-USC"))
    )
    (comp (ref "C10")
      (value "22u")
      (footprint "eagle-import:PANASONIC_C")
      (libsource (lib "eagle-import") (part "CPOL-USC"))
    )
    (comp (ref "D1")
      (value "1N5819HW")
      (footprint "eagle-import:SOD123")
      (libsource (lib "eagle-import") (part "DIODE-SOD123"))
    )
    (comp (ref "D2")
      (value "1N5819HW")
      (footprint "eagle-import:SOD123")
      (libsource (lib "eagle-import") (part "DIODE-SOD123"))
    )
    (comp (ref "IC1")
      (value "LM4040B10")
      (footprint "eagle-import:DBZ_R-PDSO-G3")
      (libsource (lib "eagle-import") (part "LM4041DBZB12"))
    )
    (comp (ref "IC2")
      (value "LM1117-3.3")
      (footprint "eagle-import:SOT223")
      (libsource (lib "eagle-import") (part "REG1117"))
    )
    (comp (ref "IC4")
      (value "LM1117-3.3")
      (footprint "eagle-import:SOT223")
      (libsource (lib "eagle-import") (part "REG1117"))
    )
    (comp (ref "JP3")
      (value "M05X2PTH")
      (footprint "eagle-import:AVR_ICSP")
      (libsource (lib "eagle-import") (part "M05X2PTH"))
    )
    (comp (ref "L1")
      (value "WE-CBF_0603")
      (footprint "eagle-import:0603")
      (libsource (lib "eagle-import") (part "WE-CBF_0603"))
    )
    (comp (ref "L2")
      (value "WE-CBF_0603")
      (footprint "eagle-import:0603")
      (libsource (lib "eagle-import") (part "WE-CBF_0603"))
    )
    (comp (ref "R1")
      (value "1.0k")
      (footprint "eagle-import:R0603")
      (libsource (lib "eagle-import") (part "R-US_R0603"))
    )
    (comp (ref "R2")
      (value "1.0k")
      (footprint "eagle-import:R0603")
      (libsource (lib "eagle-import") (part "R-US_R0603"))
    )
  )
  (nets
    (net (code "1") (name "+3V3") (class "Default")
      (node (ref "C21") (pin "1") (pinfunction "1_1") (pintype "passive"))
      (node (ref "C22") (pin "1") (pinfunction "1_1") (pintype "passive"))
      (node (ref "C33") (pin "1") (pinfunction "1_1") (pintype "passive"))
      (node (ref "C34") (pin "1") (pinfunction "1_1") (pintype "passive"))
      (node (ref "C36") (pin "1") (pinfunction "1_1") (pintype "passive"))
      (node (ref "C38") (pin "1") (pinfunction "1_1") (pintype "passive"))
      (node (ref "C39") (pin "1") (pinfunction "1_1") (pintype "passive"))
      (node (ref "C7") (pin "1") (pinfunction "1_1") (pintype "passive"))
      (node (ref "C9") (pin "+") (pinfunction "+_+") (pintype "passive"))
      (node (ref "IC10") (pin "19") (pinfunction "VDD_4_19") (pintype "power_in"))
      (node (ref "IC10") (pin "32") (pinfunction "VDD_1_32") (pintype "power_in"))
      (node (ref "IC10") (pin "48") (pinfunction "VDD_2_48") (pintype "power_in"))
      (node (ref "IC10") (pin "64") (pinfunction "VDD_3_64") (pintype "power_in"))
      (node (ref "IC12") (pin "1") (pinfunction "DBVDD_1") (pintype "bidirectional"))
      (node (ref "IC12") (pin "27") (pinfunction "DCVDD_27") (pintype "bidirectional"))
      (node (ref "IC4") (pin "2") (pinfunction "VOUT_2") (pintype "output"))
      (node (ref "JP1") (pin "1") (pinfunction "1_1") (pintype "passive"))
      (node (ref "R45") (pin "2") (pinfunction "2_2") (pintype "passive"))
      (node (ref "R52") (pin "2") (pinfunction "2_2") (pintype "passive"))
      (node (ref "R53") (pin "2") (pinfunction "2_2") (pintype "passive"))
      (node (ref "SW3") (pin "B") (pinfunction "S_B") (pintype "passive"))
      (node (ref "SW3") (pin "B'") (pinfunction "S1_B'") (pintype "passive"))
    )
    (net (code "2") (name "+3V3_A") (class "Default")
      (node (ref "C10") (pin "+") (pinfunction "+_+") (pintype "passive"))
      (node (ref "C13") (pin "1") (pinfunction "1_1") (pintype "passive"))
      (node (ref "C16") (pin "1") (pinfunction "1_1") (pintype "passive"))
      (node (ref "C17") (pin "1") (pinfunction "1_1") (pintype "passive"))
      (node (ref "C18") (pin "1") (pinfunction "1_1") (pintype "passive"))
      (node (ref "C23") (pin "1") (pinfunction "1_1") (pintype "passive"))
      (node (ref "C29") (pin "1") (pinfunction "1_1") (pintype "passive"))
      (node (ref "C32") (pin "1") (pinfunction "1_1") (pintype "passive"))
      (node (ref "C37") (pin "1") (pinfunction "1_1") (pintype "passive"))
      (node (ref "C46") (pin "1") (pinfunction "1_1") (pintype "passive"))
      (node (ref "C48") (pin "1") (pinfunction "1_1") (pintype "passive"))
      (node (ref "C51") (pin "1") (pinfunction "1_1") (pintype "passive"))
      (node (ref "C6") (pin "1") (pinfunction "1_1") (pintype "passive"))
      (node (ref "C8") (pin "1") (pinfunction "1_1") (pintype "passive"))
      (node (ref "IC10") (pin "13") (pinfunction "VDDA_13") (pintype "power_in"))
      (node (ref "IC11") (pin "16") (pinfunction "VCC_16") (pintype "power_in"))
      (node (ref "IC12") (pin "14") (pinfunction "AVDD_14") (pintype "bidirectional"))
      (node (ref "IC12") (pin "8") (pinfunction "HPVDD_8") (pintype "bidirectional"))
      (node (ref "IC13") (pin "4") (pinfunction "V+_4") (pintype "power_in"))
      (node (ref "IC2") (pin "2") (pinfunction "VOUT_2") (pintype "output"))
      (node (ref "IC3") (pin "16") (pinfunction "VCC_16") (pintype "power_in"))
      (node (ref "IC5") (pin "16") (pinfunction "VCC_16") (pintype "power_in"))
      (node (ref "IC6") (pin "4") (pinfunction "V+_4") (pintype "power_in"))
      (node (ref "IC7") (pin "4") (pinfunction "V+_4") (pintype "power_in"))
      (node (ref "IC8") (pin "16") (pinfunction "VCC_16") (pintype "power_in"))
      (node (ref "IC9") (pin "8") (pinfunction "V+_8") (pintype "power_in"))
      (node (ref "R23") (pin "P$1") (pinfunction "E_P$1") (pintype "passive"))
      (node (ref "R24") (pin "P$1") (pinfunction "E_P$1") (pintype "passive"))
      (node (ref "R25") (pin "P$1") (pinfunction "E_P$1") (pintype "passive"))
      (node (ref "R26") (pin "P$1") (pinfunction "E_P$1") (pintype "passive"))
      (node (ref "R3") (pin "P$1") (pinfunction "E_P$1") (pintype "passive"))
      (node (ref "R4") (pin "P$1") (pinfunction "E_P$1") (pintype "passive"))
      (node (ref "R5") (pin "P$1") (pinfunction "E_P$1") (pintype "passive"))
      (node (ref "R6") (pin "P$1") (pinfunction "E_P$1") (pintype "passive"))
      (node (ref "R60") (pin "2") (pinfunction "2_2") (pintype "passive"))
      (node (ref "R61") (pin "P$1") (pinfunction "E_P$1") (pintype "passive"))
      (node (ref "R62") (pin "P$1") (pinfunction "E_P$1") (pintype "passive"))
      (node (ref "R63") (pin "P$1") (pinfunction "E_P$1") (pintype "passive"))
      (node (ref "R64") (pin "P$1") (pinfunction "E_P$1") (pintype "passive"))
      (node (ref "R65") (pin "P$1") (pinfunction "E_P$1") (pintype "passive"))
      (node (ref "R66") (pin "P$1") (pinfunction "E_P$1") (pintype "passive"))
      (node (ref "R7") (pin "P$1") (pinfunction "E_P$1") (pintype "passive"))
      (node (ref "R76") (pin "P$1") (pinfunction "E_P$1") (pintype "passive"))
      (node (ref "R77") (pin "P$1") (pinfunction "E_P$1") (pintype "passive"))
      (node (ref "R78") (pin "P$1") (pinfunction "E_P$1") (pintype "passive"))
      (node (ref "R79") (pin "P$1") (pinfunction "E_P$1") (pintype "passive"))
      (node (ref "R8") (pin "P$1") (pinfunction "E_P$1") (pintype "passive"))
      (node (ref "R80") (pin "P$1") (pinfunction "E_P$1") (pintype "passive"))
      (node (ref "R81") (pin "P$1") (pinfunction "E_P$1") (pintype "passive"))
      (node (ref "R82") (pin "P$1") (pinfunction "E_P$1") (pintype "passive"))
      (node (ref "R83") (pin "P$1") (pinfunction "E_P$1") (pintype "passive"))
      (node (ref "R84") (pin "P$1") (pinfunction "E_P$1") (pintype "passive"))
      (node (ref "R85") (pin "P$1") (pinfunction "E_P$1") (pintype "passive"))
      (node (ref "R9") (pin "P$1") (pinfunction "E_P$1") (pintype "passive"))
    )
    (net (code "3") (name "ADC_ADDR_0") (class "Default")
      (node (ref "IC10") (pin "4") (pinfunction "PC15/OSC_OUT_4") (pintype "bidirectional"))
      (node (ref "IC11") (pin "11") (pinfunction "A_11") (pintype "input"))
      (node (ref "IC3") (pin "11") (pinfunction "A_11") (pintype "input"))
      (node (ref "IC5") (pin "11") (pinfunction "A_11") (pintype "input"))
      (node (ref "IC8") (pin "11") (pinfunction "A_11") (pintype "input"))
    )
    (net (code "4") (name "ADC_ADDR_1") (class "Default")
      (node (ref "IC10") (pin "3") (pinfunction "PC14/OSC32_IN_3") (pintype "bidirectional"))
      (node (ref "IC11") (pin "10") (pinfunction "B_10") (pintype "input"))
      (node (ref "IC3") (pin "10") (pinfunction "B_10") (pintype "input"))
      (node (ref "IC5") (pin "10") (pinfunction "B_10") (pintype "input"))
      (node (ref "IC8") (pin "10") (pinfunction "B_10") (pintype "input"))
    )
    (net (code "5") (name "ADC_ADDR_2") (class "Default")
      (node (ref "IC10") (pin "2") (pinfunction "PC13-TAMPER-RTC_2") (pintype "bidirectional"))
      (node (ref "IC11") (pin "9") (pinfunction "C_9") (pintype "input"))
      (node (ref "IC3") (pin "9") (pinfunction "C_9") (pintype "input"))
      (node (ref "IC5") (pin "9") (pinfunction "C_9") (pintype "input"))
      (node (ref "IC8") (pin "9") (pinfunction "C_9") (pintype "input"))
    )
    (net (code "6") (name "ADC_BANK_0") (class "Default")
      (node (ref "IC10") (pin "57") (pinfunction "PB5/I2C1_SMBA/SPI1_MOSI/SPI3_MOSI/I2S3_SD_57") (pintype "bidirectional"))
      (node (ref "IC11") (pin "6") (pinfunction "INH_6") (pintype "input"))
    )
    (net (code "7") (name "ADC_BANK_1") (class "Default")
      (node (ref "IC10") (pin "58") (pinfunction "PB6/I2C1_SCL/TIM4_CH1/USART1_TX_58") (pintype "bidirectional"))
      (node (ref "IC8") (pin "6") (pinfunction "INH_6") (pintype "input"))
    )
    (net (code "8") (name "ADC_BANK_2") (class "Default")
      (node (ref "IC10") (pin "59") (pinfunction "PB7/I2C1_SDA/TIM4_CH2/USART1_RX_59") (pintype "bidirectional"))
      (node (ref "IC5") (pin "6") (pinfunction "INH_6") (pintype "input"))
    )
    (net (code "9") (name "ADC_BANK_3") (class "Default")
      (node (ref "IC10") (pin "61") (pinfunction "PB8/TIM4_CH3/I2C1_SCL_61") (pintype "bidirectional"))
      (node (ref "IC3") (pin "6") (pinfunction "INH_6") (pintype "input"))
    )
    (net (code "10") (name "ADC_BLOW_SHAPE") (class "Default")
      (node (ref "C15") (pin "2") (pinfunction "2_2") (pintype "passive"))
      (node (ref "IC10") (pin "16") (pinfunction "PA2/USART2_TX/ADC2/TIM2_CH3_16") (pintype "bidirectional"))
      (node (ref "IC6") (pin "8") (pinfunction "OUT_8") (pintype "output"))
      (node (ref "R12") (pin "1") (pinfunction "1_1") (pintype "passive"))
    )
    (net (code "11") (name "ADC_BLOW_TIMBRE") (class "Default")
      (node (ref "C27") (pin "2") (pinfunction "2_2") (pintype "passive"))
      (node (ref "IC10") (pin "17") (pinfunction "PA3/USART2_RX/ADC3/TIM2_CH4_17") (pintype "bidirectional"))
      (node (ref "IC6") (pin "7") (pinfunction "OUT_7") (pintype "output"))
      (node (ref "R35") (pin "1") (pinfunction "1_1") (pintype "passive"))
    )
    (net (code "12") (name "ADC_BOW_TIMBRE") (class "Default")
      (node (ref "C14") (pin "2") (pinfunction "2_2") (pintype "passive"))
      (node (ref "IC10") (pin "15") (pinfunction "PA1/USART2_RTS/UART4_RX/ADC1/TIM2_CH2_15") (pintype "bidirectional"))
      (node (ref "IC6") (pin "14") (pinfunction "OUT_14") (pintype "output"))
      (node (ref "R11") (pin "1") (pinfunction "1_1") (pintype "passive"))
    )
    (net (code "13") (name "ADC_BRIGHTNESS") (class "Default")
      (node (ref "C42") (pin "2") (pinfunction "2_2") (pintype "passive"))
      (node (ref "IC10") (pin "26") (pinfunction "PB0/ADC8/TIM3_CH3_26") (pintype "bidirectional"))
      (node (ref "IC13") (pin "8") (pinfunction "OUT_8") (pintype "output"))
      (node (ref "R49") (pin "1") (pinfunction "1_1") (pintype "passive"))
    )
    (net (code "14") (name "ADC_DAMPING") (class "Default")
      (node (ref "C20") (pin "2") (pinfunction "2_2") (pintype "passive"))
      (node (ref "IC10") (pin "22") (pinfunction "PA6/SPI1_MISO/ADC6/TIM3_CH1_22") (pintype "bidirectional"))
      (node (ref "IC7") (pin "8") (pinfunction "OUT_8") (pintype "output"))
      (node (ref "R18") (pin "1") (pinfunction "1_1") (pintype "passive"))
    )
    (net (code "15") (name "ADC_FM") (class "Default")
      (node (ref "C25") (pin "2") (pinfunction "2_2") (pintype "passive"))
      (node (ref "IC10") (pin "11") (pinfunction "PC3/SPI2_MOSI/I2S2_SD/ADC13_11") (pintype "bidirectional"))
      (node (ref "IC9") (pin "7") (pinfunction "OUT_7") (pintype "output"))
      (node (ref "R28") (pin "1") (pinfunction "1_1") (pintype "passive"))
    )
    (net (code "16") (name "ADC_GEOMETRY") (class "Default")
      (node (ref "C28") (pin "2") (pinfunction "2_2") (pintype "passive"))
      (node (ref "IC10") (pin "23") (pinfunction "PA7/SPI1_MOSI/ADC7/TIM3_CH2_23") (pintype "bidirectional"))
      (node (ref "IC7") (pin "7") (pinfunction "OUT_7") (pintype "output"))
      (node (ref "R29") (pin "1") (pinfunction "1_1") (pintype "passive"))
    )
    (net (code "17") (name "ADC_POSITION") (class "Default")
      (node (ref "C41") (pin "2") (pinfunction "2_2") (pintype "passive"))
      (node (ref "IC10") (pin "25") (pinfunction "PC5/ADC15_25") (pintype "bidirectional"))
      (node (ref "IC13") (pin "14") (pinfunction "OUT_14") (pintype "output"))
      (node (ref "R48") (pin "1") (pinfunction "1_1") (pintype "passive"))
    )
    (net (code "18") (name "ADC_POTS") (class "Default")
      (node (ref "IC10") (pin "8") (pinfunction "PC0/ADC10_8") (pintype "bidirectional"))
      (node (ref "IC11") (pin "3") (pinfunction "X_3") (pintype "bidirectional"))
      (node (ref "IC3") (pin "3") (pinfunction "X_3") (pintype "bidirectional"))
      (node (ref "IC5") (pin "3") (pinfunction "X_3") (pintype "bidirectional"))
      (node (ref "IC8") (pin "3") (pinfunction "X_3") (pintype "bidirectional"))
      (node (ref "TP1") (pin "P$1") (pinfunction "1_P$1") (pintype "bidirectional"))
    )
    (net (code "19") (name "ADC_PRESSURE") (class "Default")
      (node (ref "C26") (pin "2") (pinfunction "2_2") (pintype "passive"))
      (node (ref "IC10") (pin "14") (pinfunction "PA0-WKUP/USART2_CTS/UART4_TX/ADC0/TIM2_CH1_ETR_14") (pintype "bidirectional"))
      (node (ref "IC6") (pin "1") (pinfunction "OUT_1") (pintype "output"))
      (node (ref "R34") (pin "1") (pinfunction "1_1") (pintype "passive"))
    )
    (net (code "20") (name "ADC_SPACE") (class "Default")
      (node (ref "C50") (pin "2") (pinfunction "2_2") (pintype "passive"))
      (node (ref "IC10") (pin "27") (pinfunction "PB1/ADC9/TIM3_CH4_27") (pintype "bidirectional"))
      (node (ref "IC13") (pin "7") (pinfunction "OUT_7") (pintype "output"))
      (node (ref "R73") (pin "1") (pinfunction "1_1") (pintype "passive"))
    )
    (net (code "21") (name "ADC_STRIKE_SHAPE") (class "Default")
      (node (ref "C30") (pin "2") (pinfunction "2_2") (pintype "passive"))
      (node (ref "IC10") (pin "20") (pinfunction "PA4/SPI1_NSS/SPI3_NSS/USART2_CK/I2S3_WS/ADC4/DAC1_20") (pintype "bidirectional"))
      (node (ref "IC7") (pin "1") (pinfunction "OUT_1") (pintype "output"))
      (node (ref "R46") (pin "1") (pinfunction "1_1") (pintype "passive"))
    )
    (net (code "22") (name "ADC_STRIKE_TIMBRE") (class "Default")
      (node (ref "C19") (pin "2") (pinfunction "2_2") (pintype "passive"))
      (node (ref "IC10") (pin "21") (pinfunction "PA5/SPI1_SCK/ADC5/DAC2_21") (pintype "bidirectional"))
      (node (ref "IC7") (pin "14") (pinfunction "OUT_14") (pintype "output"))
      (node (ref "R17") (pin "1") (pinfunction "1_1") (pintype "passive"))
    )
    (net (code "23") (name "ADC_V_OCT") (class "Default")
      (node (ref "C24") (pin "2") (pinfunction "2_2") (pintype "passive"))
      (node (ref "IC10") (pin "10") (pinfunction "PC2/SPI2_MISO/ADC12_10") (pintype "bidirectional"))
      (node (ref "IC9") (pin "1") (pinfunction "OUT_1") (pintype "output"))
      (node (ref "R27") (pin "1") (pinfunction "1_1") (pintype "passive"))
    )
    (net (code "24") (name "AREF_-10") (class "Default")
      (node (ref "C2") (pin "1") (pinfunction "1_1") (pintype "passive"))
      (node (ref "IC1") (pin "2") (pinfunction "A_2") (pintype "passive"))
      (node (ref "R1") (pin "2") (pinfunction "2_2") (pintype "passive"))
      (node (ref "R14") (pin "2") (pinfunction "2_2") (pintype "passive"))
      (node (ref "R15") (pin "2") (pinfunction "2_2") (pintype "passive"))
      (node (ref "R2") (pin "2") (pinfunction "2_2") (pintype "passive"))
      (node (ref "R20") (pin "2") (pinfunction "2_2") (pintype "passive"))
      (node (ref "R21") (pin "2") (pinfunction "2_2") (pintype "passive"))
      (node (ref "R31") (pin "2") (pinfunction "2_2") (pintype "passive"))
      (node (ref "R32") (pin "2") (pinfunction "2_2") (pintype "passive"))
      (node (ref "R37") (pin "2") (pinfunction "2_2") (pintype "passive"))
      (node (ref "R38") (pin "2") (pinfunction "2_2") (pintype "passive"))
      (node (ref "R41") (pin "2") (pinfunction "2_2") (pintype "passive"))
      (node (ref "R42") (pin "2") (pinfunction "2_2") (pintype "passive"))
      (node (ref "R55") (pin "2") (pinfunction "2_2") (pintype "passive"))
      (node (ref "R56") (pin "2") (pinfunction "2_2") (pintype "passive"))
      (node (ref "R70") (pin "2") (pinfunction "2_2") (pintype "passive"))
    )
    (net (code "25") (name "BOOT_FLASH") (class "Default")
      (node (ref "IC10") (pin "60") (pinfunction "BOOT0_60") (pintype "bidirectional"))
      (node (ref "R50") (pin "2") (pinfunction "2_2") (pintype "passive"))
      (node (ref "SW3") (pin "A") (pinfunction "P_A") (pintype "passive"))
      (node (ref "SW3") (pin "A'") (pinfunction "P1_A'") (pintype "passive"))
    )
    (net (code "26") (name "GATE") (class "Default")
      (node (ref "IC10") (pin "24") (pinfunction "PC4/ADC14_24") (pintype "bidirectional"))
      (node (ref "Q2") (pin "C") (pinfunction "C_C") (pintype "passive"))
      (node (ref "R60") (pin "1") (pinfunction "1_1") (pintype "passive"))
    )
    (net (code "27") (name "GND") (class "Default")
      (node (ref "C1") (pin "+") (pinfunction "+_+") (pintype "passive"))
      (node (ref "C10") (pin "-") (pinfunction "-_-") (pintype "passive"))
      (node (ref "C11") (pin "1") (pinfunction "1_1") (pintype "passive"))
      (node (ref "C12") (pin "1") (pinfunction "1_1") (pintype "passive"))
      (node (ref "C13") (pin "2") (pinfunction "2_2") (pintype "passive"))
      (node (ref "C16") (pin "2") (pinfunction "2_2") (pintype "passive"))
      (node (ref "C17") (pin "2") (pinfunction "2_2") (pintype "passive"))
      (node (ref "C18") (pin "2") (pinfunction "2_2") (pintype "passive"))
      (node (ref "C2") (pin "2") (pinfunction "2_2") (pintype "passive"))
      (node (ref "C21") (pin "2") (pinfunction "2_2") (pintype "passive"))
      (node (ref "C22") (pin "2") (pinfunction "2_2") (pintype "passive"))
      (node (ref "C23") (pin "2") (pinfunction "2_2") (pintype "passive"))
      (node (ref "C29") (pin "2") (pinfunction "2_2") (pintype "passive"))
      (node (ref "C3") (pin "-") (pinfunction "-_-") (pintype "passive"))
      (node (ref "C31") (pin "2") (pinfunction "2_2") (pintype "passive"))
      (node (ref "C32") (pin "2") (pinfunction "2_2") (pintype "passive"))
      (node (ref "C33") (pin "2") (pinfunction "2_2") (pintype "passive"))
      (node (ref "C34") (pin "2") (pinfunction "2_2") (pintype "passive"))
      (node (ref "C35") (pin "2") (pinfunction "2_2") (pintype "passive"))
      (node (ref "C36") (pin "2") (pinfunction "2_2") (pintype "passive"))
      (node (ref "C37") (pin "2") (pinfunction "2_2") (pintype "passive"))
      (node (ref "C38") (pin "2") (pinfunction "2_2") (pintype "passive"))
      (node (ref "C39") (pin "2") (pinfunction "2_2") (pintype "passive"))
      (node (ref "C4") (pin "2") (pinfunction "2_2") (pintype "passive"))
      (node (ref "C44") (pin "2") (pinfunction "2_2") (pintype "passive"))
      (node (ref "C45") (pin "1") (pinfunction "1_1") (pintype "passive"))
      (node (ref "C46") (pin "2") (pinfunction "2_2") (pintype "passive"))
      (node (ref "C47") (pin "2") (pinfunction "2_2") (pintype "passive"))
      (node (ref "C48") (pin "2") (pinfunction "2_2") (pintype "passive"))
      (node (ref "C5") (pin "2") (pinfunction "2_2") (pintype "passive"))
      (node (ref "C51") (pin "2") (pinfunction "2_2") (pintype "passive"))
      (node (ref "C52") (pin "-") (pinfunction "-_-") (pintype "passive"))
      (node (ref "C54") (pin "2") (pinfunction "2_2") (pintype "passive"))
      (node (ref "C57") (pin "2") (pinfunction "2_2") (pintype "passive"))
      (node (ref "C6") (pin "2") (pinfunction "2_2") (pintype "passive"))
      (node (ref "C7") (pin "2") (pinfunction "2_2") (pintype "passive"))
      (node (ref "C8") (pin "2") (pinfunction "2_2") (pintype "passive"))
      (node (ref "C9") (pin "-") (pinfunction "-_-") (pintype "passive"))
      (node (ref "IC1") (pin "1") (pinfunction "C_1") (pintype "passive"))
      (node (ref "IC10") (pin "12") (pinfunction "VSSA_12") (pintype "power_in"))
      (node (ref "IC10") (pin "18") (pinfunction "VSS_4_18") (pintype "power_in"))
      (node (ref "IC10") (pin "28") (pinfunction "PB2/BOOT1_28") (pintype "bidirectional"))
      (node (ref "IC10") (pin "63") (pinfunction "VSS_3_63") (pintype "power_in"))
      (node (ref "IC11") (pin "12") (pinfunction "X3_12") (pintype "bidirectional"))
      (node (ref "IC11") (pin "7") (pinfunction "VEE_7") (pintype "power_in"))
      (node (ref "IC11") (pin "8") (pinfunction "GND_8") (pintype "power_in"))
      (node (ref "IC12") (pin "11") (pinfunction "HPGND_11") (pintype "bidirectional"))
      (node (ref "IC12") (pin "15") (pinfunction "AGND_15") (pintype "bidirectional"))
      (node (ref "IC12") (pin "21") (pinfunction "MODE_21") (pintype "bidirectional"))
      (node (ref "IC12") (pin "22") (pinfunction "CSB_22") (pintype "bidirectional"))
      (node (ref "IC12") (pin "28") (pinfunction "DGND_28") (pintype "bidirectional"))
      (node (ref "IC13") (pin "10") (pinfunction "+IN_10") (pintype "input"))
      (node (ref "IC13") (pin "11") (pinfunction "V-_11") (pintype "power_in"))
      (node (ref "IC13") (pin "12") (pinfunction "+IN_12") (pintype "input"))
      (node (ref "IC13") (pin "3") (pinfunction "+IN_3") (pintype "input"))
      (node (ref "IC13") (pin "5") (pinfunction "+IN_5") (pintype "input"))
      (node (ref "IC14") (pin "3") (pinfunction "+IN_3") (pintype "input"))
      (node (ref "IC14") (pin "5") (pinfunction "+IN_5") (pintype "input"))
      (node (ref "IC2") (pin "1") (pinfunction "GND_1") (pintype "power_in"))
      (node (ref "IC3") (pin "7") (pinfunction "VEE_7") (pintype "power_in"))
      (node (ref "IC3") (pin "8") (pinfunction "GND_8") (pintype "power_in"))
      (node (ref "IC4") (pin "1") (pinfunction "GND_1") (pintype "power_in"))
      (node (ref "IC5") (pin "7") (pinfunction "VEE_7") (pintype "power_in"))
      (node (ref "IC5") (pin "8") (pinfunction "GND_8") (pintype "power_in"))
      (node (ref "IC6") (pin "10") (pinfunction "+IN_10") (pintype "input"))
      (node (ref "IC6") (pin "11") (pinfunction "V-_11") (pintype "power_in"))
      (node (ref "IC6") (pin "12") (pinfunction "+IN_12") (pintype "input"))
      (node (ref "IC6") (pin "3") (pinfunction "+IN_3") (pintype "input"))
      (node (ref "IC6") (pin "5") (pinfunction "+IN_5") (pintype "input"))
      (node (ref "IC7") (pin "10") (pinfunction "+IN_10") (pintype "input"))
      (node (ref "IC7") (pin "11") (pinfunction "V-_11") (pintype "power_in"))
      (node (ref "IC7") (pin "12") (pinfunction "+IN_12") (pintype "input"))
      (node (ref "IC7") (pin "3") (pinfunction "+IN_3") (pintype "input"))
      (node (ref "IC7") (pin "5") (pinfunction "+IN_5") (pintype "input"))
      (node (ref "IC8") (pin "1") (pinfunction "X4_1") (pintype "bidirectional"))
      (node (ref "IC8") (pin "2") (pinfunction "X6_2") (pintype "bidirectional"))
      (node (ref "IC8") (pin "4") (pinfunction "X7_4") (pintype "bidirectional"))
      (node (ref "IC8") (pin "5") (pinfunction "X5_5") (pintype "bidirectional"))
      (node (ref "IC8") (pin "7") (pinfunction "VEE_7") (pintype "power_in"))
      (node (ref "IC8") (pin "8") (pinfunction "GND_8") (pintype "power_in"))
      (node (ref "IC9") (pin "3") (pinfunction "+IN_3") (pintype "input"))
      (node (ref "IC9") (pin "4") (pinfunction "V-_4") (pintype "power_in"))
      (node (ref "IC9") (pin "5") (pinfunction "+IN_5") (pintype "input"))
      (node (ref "J1") (pin "P1") (pinfunction "1_P1") (pintype "passive"))
      (node (ref "J10") (pin "P1") (pinfunction "1_P1") (pintype "passive"))
      (node (ref "J11") (pin "P1") (pinfunction "1_P1") (pintype "passive"))
      (node (ref "J12") (pin "P1") (pinfunction "1_P1") (pintype "passive"))
      (node (ref "J13") (pin "P1") (pinfunction "1_P1") (pintype "passive"))
      (node (ref "J14") (pin "P1") (pinfunction "1_P1") (pintype "passive"))
      (node (ref "J15") (pin "P1") (pinfunction "1_P1") (pintype "passive"))
      (node (ref "J16") (pin "P1") (pinfunction "1_P1") (pintype "passive"))
      (node (ref "J17") (pin "P1") (pinfunction "1_P1") (pintype "passive"))
      (node (ref "J18") (pin "P1") (pinfunction "1_P1") (pintype "passive"))
      (node (ref "J2") (pin "P1") (pinfunction "1_P1") (pintype "passive"))
      (node (ref "J3") (pin "P1") (pinfunction "1_P1") (pintype "passive"))
      (node (ref "J3") (pin "P2") (pinfunction "2_P2") (pintype "passive"))
      (node (ref "J4") (pin "P1") (pinfunction "1_P1") (pintype "passive"))
      (node (ref "J5") (pin "P1") (pinfunction "1_P1") (pintype "passive"))
      (node (ref "J6") (pin "P1") (pinfunction "1_P1") (pintype "passive"))
      (node (ref "J7") (pin "P1") (pinfunction "1_P1") (pintype "passive"))
      (node (ref "J8") (pin "P1") (pinfunction "1_P1") (pintype "passive"))
      (node (ref "J9") (pin "P1") (pinfunction "1_P1") (pintype "passive"))
      (node (ref "JP1") (pin "3") (pinfunction "3_3") (pintype "passive"))
      (node (ref "JP1") (pin "5") (pinfunction "5_5") (pintype "passive"))
      (node (ref "JP1") (pin "9") (pinfunction "9_9") (pintype "passive"))
      (node (ref "JP2") (pin "1") (pinfunction "1_1") (pintype "passive"))
      (node (ref "JP3") (pin "3") (pinfunction "3_3") (pintype "passive"))
      (node (ref "JP3") (pin "4") (pinfunction "4_4") (pintype "passive"))
      (node (ref "JP3") (pin "5") (pinfunction "5_5") (pintype "passive"))
      (node (ref "JP3") (pin "6") (pinfunction "6_6") (pintype "passive"))
      (node (ref "JP3") (pin "7") (pinfunction "7_7") (pintype "passive"))
      (node (ref "JP3") (pin "8") (pinfunction "8_8") (pintype "passive"))
      (node (ref "LED1") (pin "K") (pinfunction "C_K") (pintype "passive"))
      (node (ref "LED2") (pin "K") (pinfunction "C_K") (pintype "passive"))
      (node (ref "Q2") (pin "E") (pinfunction "E_E") (pintype "passive"))
      (node (ref "R23") (pin "P$3") (pinfunction "A_P$3") (pintype "passive"))
      (node (ref "R24") (pin "P$3") (pinfunction "A_P$3") (pintype "passive"))
      (node (ref "R25") (pin "P$3") (pinfunction "A_P$3") (pintype "passive"))
      (node (ref "R26") (pin "P$3") (pinfunction "A_P$3") (pintype "passive"))
      (node (ref "R3") (pin "P$3") (pinfunction "A_P$3") (pintype "passive"))
      (node (ref "R4") (pin "P$3") (pinfunction "A_P$3") (pintype "passive"))
      (node (ref "R5") (pin "P$3") (pinfunction "A_P$3") (pintype "passive"))
      (node (ref "R50") (pin "1") (pinfunction "1_1") (pintype "passive"))
      (node (ref "R59") (pin "1") (pinfunction "1_1") (pintype "passive"))
      (node (ref "R6") (pin "P$3") (pinfunction "A_P$3") (pintype "passive"))
      (node (ref "R61") (pin "P$3") (pinfunction "A_P$3") (pintype "passive"))
      (node (ref "R62") (pin "P$3") (pinfunction "A_P$3") (pintype "passive"))
      (node (ref "R63") (pin "P$3") (pinfunction "A_P$3") (pintype "passive"))
      (node (ref "R64") (pin "P$3") (pinfunction "A_P$3") (pintype "passive"))
      (node (ref "R65") (pin "P$3") (pinfunction "A_P$3") (pintype "passive"))
      (node (ref "R66") (pin "P$3") (pinfunction "A_P$3") (pintype "passive"))
      (node (ref "R69") (pin "1") (pinfunction "1_1") (pintype "passive"))
      (node (ref "R7") (pin "P$3") (pinfunction "A_P$3") (pintype "passive"))
      (node (ref "R74") (pin "1") (pinfunction "1_1") (pintype "passive"))
      (node (ref "R76") (pin "P$3") (pinfunction "A_P$3") (pintype "passive"))
      (node (ref "R77") (pin "P$3") (pinfunction "A_P$3") (pintype "passive"))
      (node (ref "R78") (pin "P$3") (pinfunction "A_P$3") (pintype "passive"))
      (node (ref "R79") (pin "P$3") (pinfunction "A_P$3") (pintype "passive"))
      (node (ref "R8") (pin "P$3") (pinfunction "A_P$3") (pintype "passive"))
      (node (ref "R80") (pin "P$3") (pinfunction "A_P$3") (pintype "passive"))
      (node (ref "R81") (pin "P$3") (pinfunction "A_P$3") (pintype "passive"))
      (node (ref "R82") (pin "P$3") (pinfunction "A_P$3") (pintype "passive"))
      (node (ref "R83") (pin "P$3") (pinfunction "A_P$3") (pintype "passive"))
      (node (ref "R84") (pin "P$3") (pinfunction "A_P$3") (pintype "passive"))
      (node (ref "R85") (pin "P$3") (pinfunction "A_P$3") (pintype "passive"))
      (node (ref "R87") (pin "1") (pinfunction "1_1") (pintype "passive"))
      (node (ref "R9") (pin "P$3") (pinfunction "A_P$3") (pintype "passive"))
      (node (ref "SW1") (pin "L2") (pinfunction "L2_L2") (pintype "passive"))
      (node (ref "SW1") (pin "P3") (pinfunction "A3_P3") (pintype "passive"))
      (node (ref "SW1") (pin "P6") (pinfunction "B3_P6") (pintype "passive"))
      (node (ref "SW2") (pin "A") (pinfunction "P_A") (pintype "passive"))
      (node (ref "SW2") (pin "A'") (pinfunction "P1_A'") (pintype "passive"))
    )
    (net (code "28") (name "I2C_SCL") (class "Default")
      (node (ref "IC10") (pin "29") (pinfunction "PB10/SPI2_SCK/I2S_SCK/I2C2_SCL/USART3_TX_29") (pintype "bidirectional"))
      (node (ref "IC12") (pin "24") (pinfunction "SCLK_24") (pintype "bidirectional"))
      (node (ref "R52") (pin "1") (pinfunction "1_1") (pintype "passive"))
    )
    (net (code "29") (name "I2C_SDA") (class "Default")
      (node (ref "IC10") (pin "30") (pinfunction "PB11/I2C2_SDA/USART3_RX_30") (pintype "bidirectional"))
      (node (ref "IC12") (pin "23") (pinfunction "SDIN_23") (pintype "bidirectional"))
      (node (ref "R53") (pin "1") (pinfunction "1_1") (pintype "passive"))
    )
    (net (code "30") (name "I2S_LRCK") (class "Default")
      (node (ref "IC10") (pin "33") (pinfunction "PB12/SPI2_NSS/I2S2_WS/I2C2_SMBA/USART3_CK/TIM1_BKIN_33") (pintype "bidirectional"))
      (node (ref "IC12") (pin "5") (pinfunction "DACLRC_5") (pintype "bidirectional"))
      (node (ref "IC12") (pin "7") (pinfunction "ADCLRC_7") (pintype "bidirectional"))
    )
    (net (code "31") (name "I2S_MCK") (class "Default")
      (node (ref "IC10") (pin "37") (pinfunction "PC6/I2S2_MCK_37") (pintype "bidirectional"))
      (node (ref "IC12") (pin "25") (pinfunction "XTI/MCLK_25") (pintype "bidirectional"))
    )
    (net (code "32") (name "I2S_SCK") (class "Default")
      (node (ref "IC10") (pin "34") (pinfunction "PB13/SPI2_SCK/I2S2_SCK/USART3_CTS/TIM1_CH1N_34") (pintype "bidirectional"))
      (node (ref "IC12") (pin "3") (pinfunction "BCLK_3") (pintype "bidirectional"))
    )
    (net (code "33") (name "I2S_SIN") (class "Default")
      (node (ref "IC10") (pin "35") (pinfunction "PB14/SPI2_MISO/USART3_RTS/TIM1_CH2N_35") (pintype "bidirectional"))
      (node (ref "IC12") (pin "6") (pinfunction "ADCDAT_6") (pintype "bidirectional"))
    )
    (net (code "34") (name "I2S_SOUT") (class "Default")
      (node (ref "IC10") (pin "36") (pinfunction "PB15/SPI2_MOSI/I2S2_SD/TIM1_CH3N_36") (pintype "bidirectional"))
      (node (ref "IC12") (pin "4") (pinfunction "DACDAT_4") (pintype "bidirectional"))
    )
    (net (code "35") (name "JTCK") (class "Default")
      (node (ref "IC10") (pin "49") (pinfunction "PA14/JTCK-SWCLK_49") (pintype "bidirectional"))
      (node (ref "JP1") (pin "4") (pinfunction "4_4") (pintype "passive"))
    )
    (net (code "36") (name "JTDI") (class "Default")
      (node (ref "IC10") (pin "50") (pinfunction "PA15/JTDI/SPI3_NSS/I2S3_WS_50") (pintype "bidirectional"))
      (node (ref "JP1") (pin "8") (pinfunction "8_8") (pintype "passive"))
    )
    (net (code "37") (name "JTDO") (class "Default")
      (node (ref "IC10") (pin "55") (pinfunction "PB3/JTDO/SPI3_SCK/I2S3_SCK_55") (pintype "bidirectional"))
      (node (ref "JP1") (pin "6") (pinfunction "6_6") (pintype "passive"))
    )
    (net (code "38") (name "JTMS") (class "Default")
      (node (ref "IC10") (pin "46") (pinfunction "PA13/JTMS-SWDAT_46") (pintype "bidirectional"))
      (node (ref "JP1") (pin "2") (pinfunction "2_2") (pintype "passive"))
    )
    (net (code "39") (name "LED_GATE") (class "Default")
      (node (ref "IC10") (pin "38") (pinfunction "PC7/I2S3_MCK_38") (pintype "bidirectional"))
      (node (ref "R10") (pin "1") (pinfunction "1_1") (pintype "passive"))
    )
    (net (code "40") (name "LIN") (class "Default")
      (node (ref "C56") (pin "+") (pinfunction "+_+") (pintype "passive"))
      (node (ref "IC12") (pin "20") (pinfunction "LLINEIN_20") (pintype "bidirectional"))
    )
    (net (code "41") (name "LOUT") (class "Default")
      (node (ref "C40") (pin "+") (pinfunction "+_+") (pintype "passive"))
      (node (ref "IC12") (pin "12") (pinfunction "LOUT_12") (pintype "bidirectional"))
    )
    (net (code "42") (name "Net-(C40-Pad-)") (class "Default")
      (node (ref "C40") (pin "-") (pinfunction "-_-") (pintype "passive"))
      (node (ref "R58") (pin "2") (pinfunction "2_2") (pintype "passive"))
      (node (ref "R59") (pin "2") (pinfunction "2_2") (pintype "passive"))
    )
    (net (code "43") (name "Net-(C53-Pad-)") (class "Default")
      (node (ref "C53") (pin "-") (pinfunction "-_-") (pintype "passive"))
      (node (ref "R68") (pin "2") (pinfunction "2_2") (pintype "passive"))
      (node (ref "R69") (pin "2") (pinfunction "2_2") (pintype "passive"))
    )
    (net (code "44") (name "Net-(C54-Pad1)") (class "Default")
      (node (ref "C54") (pin "1") (pinfunction "1_1") (pintype "passive"))
      (node (ref "C55") (pin "-") (pinfunction "-_-") (pintype "passive"))
      (node (ref "R74") (pin "2") (pinfunction "2_2") (pintype "passive"))
      (node (ref "R75") (pin "1") (pinfunction "1_1") (pintype "passive"))
    )
    (net (code "45") (name "Net-(C56-Pad-)") (class "Default")
      (node (ref "C56") (pin "-") (pinfunction "-_-") (pintype "passive"))
      (node (ref "C57") (pin "1") (pinfunction "1_1") (pintype "passive"))
      (node (ref "R86") (pin "1") (pinfunction "1_1") (pintype "passive"))
      (node (ref "R87") (pin "2") (pinfunction "2_2") (pintype "passive"))
    )
    (net (code "46") (name "Net-(D1-PadA)") (class "Default")
      (node (ref "D1") (pin "A") (pinfunction "A_A") (pintype "passive"))
      (node (ref "JP3") (pin "1") (pinfunction "1_1") (pintype "passive"))
      (node (ref "JP3") (pin "2") (pinfunction "2_2") (pintype "passive"))
    )
    (net (code "47") (name "Net-(D2-PadC)") (class "Default")
      (node (ref "D2") (pin "C") (pinfunction "C_C") (pintype "passive"))
      (node (ref "JP3") (pin "10") (pinfunction "10_10") (pintype "passive"))
      (node (ref "JP3") (pin "9") (pinfunction "9_9") (pintype "passive"))
    )
    (net (code "48") (name "Net-(IC2-VIN)") (class "Default")
      (node (ref "C4") (pin "1") (pinfunction "1_1") (pintype "passive"))
      (node (ref "IC2") (pin "3") (pinfunction "VIN_3") (pintype "input"))
      (node (ref "L2") (pin "2") (pinfunction "2_2") (pintype "passive"))
    )
    (net (code "49") (name "Net-(IC3A-X0)") (class "Default")
      (node (ref "IC3") (pin "13") (pinfunction "X0_13") (pintype "bidirectional"))
      (node (ref "R26") (pin "P$2") (pinfunction "S_P$2") (pintype "passive"))
    )
    (net (code "50") (name "Net-(IC3A-X1)") (class "Default")
      (node (ref "IC3") (pin "14") (pinfunction "X1_14") (pintype "bidirectional"))
      (node (ref "R9") (pin "P$2") (pinfunction "S_P$2") (pintype "passive"))
    )
    (net (code "51") (name "Net-(IC3A-X2)") (class "Default")
      (node (ref "IC3") (pin "15") (pinfunction "X2_15") (pintype "bidirectional"))
      (node (ref "R8") (pin "P$2") (pinfunction "S_P$2") (pintype "passive"))
    )
    (net (code "52") (name "Net-(IC3A-X3)") (class "Default")
      (node (ref "IC3") (pin "12") (pinfunction "X3_12") (pintype "bidirectional"))
      (node (ref "R66") (pin "P$2") (pinfunction "S_P$2") (pintype "passive"))
    )
    (net (code "53") (name "Net-(IC3A-X4)") (class "Default")
      (node (ref "IC3") (pin "1") (pinfunction "X4_1") (pintype "bidirectional"))
      (node (ref "R3") (pin "P$2") (pinfunction "S_P$2") (pintype "passive"))
    )
    (net (code "54") (name "Net-(IC3A-X5)") (class "Default")
      (node (ref "IC3") (pin "5") (pinfunction "X5_5") (pintype "bidirectional"))
      (node (ref "R5") (pin "P$2") (pinfunction "S_P$2") (pintype "passive"))
    )
    (net (code "55") (name "Net-(IC3A-X6)") (class "Default")
      (node (ref "IC3") (pin "2") (pinfunction "X6_2") (pintype "bidirectional"))
      (node (ref "R4") (pin "P$2") (pinfunction "S_P$2") (pintype "passive"))
    )
    (net (code "56") (name "Net-(IC3A-X7)") (class "Default")
      (node (ref "IC3") (pin "4") (pinfunction "X7_4") (pintype "bidirectional"))
      (node (ref "R25") (pin "P$2") (pinfunction "S_P$2") (pintype "passive"))
    )
    (net (code "57") (name "Net-(IC4-VIN)") (class "Default")
      (node (ref "C5") (pin "1") (pinfunction "1_1") (pintype "passive"))
      (node (ref "IC4") (pin "3") (pinfunction "VIN_3") (pintype "input"))
      (node (ref "L1") (pin "2") (pinfunction "2_2") (pintype "passive"))
    )
    (net (code "58") (name "Net-(IC5A-X0)") (class "Default")
      (node (ref "IC5") (pin "13") (pinfunction "X0_13") (pintype "bidirectional"))
      (node (ref "R83") (pin "P$2") (pinfunction "S_P$2") (pintype "passive"))
    )
    (net (code "59") (name "Net-(IC5A-X1)") (class "Default")
      (node (ref "IC5") (pin "14") (pinfunction "X1_14") (pintype "bidirectional"))
      (node (ref "R84") (pin "P$2") (pinfunction "S_P$2") (pintype "passive"))
    )
    (net (code "60") (name "Net-(IC5A-X2)") (class "Default")
      (node (ref "IC5") (pin "15") (pinfunction "X2_15") (pintype "bidirectional"))
      (node (ref "R85") (pin "P$2") (pinfunction "S_P$2") (pintype "passive"))
    )
    (net (code "61") (name "Net-(IC5A-X3)") (class "Default")
      (node (ref "IC5") (pin "12") (pinfunction "X3_12") (pintype "bidirectional"))
      (node (ref "R82") (pin "P$2") (pinfunction "S_P$2") (pintype "passive"))
    )
    (net (code "62") (name "Net-(IC5A-X4)") (class "Default")
      (node (ref "IC5") (pin "1") (pinfunction "X4_1") (pintype "bidirectional"))
      (node (ref "R23") (pin "P$2") (pinfunction "S_P$2") (pintype "passive"))
    )
    (net (code "63") (name "Net-(IC5A-X5)") (class "Default")
      (node (ref "IC5") (pin "5") (pinfunction "X5_5") (pintype "bidirectional"))
      (node (ref "R24") (pin "P$2") (pinfunction "S_P$2") (pintype "passive"))
    )
    (net (code "64") (name "Net-(IC5A-X6)") (class "Default")
      (node (ref "IC5") (pin "2") (pinfunction "X6_2") (pintype "bidirectional"))
      (node (ref "R6") (pin "P$2") (pinfunction "S_P$2") (pintype "passive"))
    )
    (net (code "65") (name "Net-(IC5A-X7)") (class "Default")
      (node (ref "IC5") (pin "4") (pinfunction "X7_4") (pintype "bidirectional"))
      (node (ref "R7") (pin "P$2") (pinfunction "S_P$2") (pintype "passive"))
    )
    (net (code "66") (name "Net-(IC6A--IN)") (class "Default")
      (node (ref "C26") (pin "1") (pinfunction "1_1") (pintype "passive"))
      (node (ref "IC6") (pin "2") (pinfunction "-IN_2") (pintype "input"))
      (node (ref "R30") (pin "1") (pinfunction "1_1") (pintype "passive"))
      (node (ref "R31") (pin "1") (pinfunction "1_1") (pintype "passive"))
      (node (ref "R34") (pin "2") (pinfunction "2_2") (pintype "passive"))
    )
    (net (code "67") (name "Net-(IC6B--IN)") (class "Default")
      (node (ref "C27") (pin "1") (pinfunction "1_1") (pintype "passive"))
      (node (ref "IC6") (pin "6") (pinfunction "-IN_6") (pintype "input"))
      (node (ref "R32") (pin "1") (pinfunction "1_1") (pintype "passive"))
      (node (ref "R33") (pin "1") (pinfunction "1_1") (pintype "passive"))
      (node (ref "R35") (pin "2") (pinfunction "2_2") (pintype "passive"))
    )
    (net (code "68") (name "Net-(IC6C--IN)") (class "Default")
      (node (ref "C15") (pin "1") (pinfunction "1_1") (pintype "passive"))
      (node (ref "IC6") (pin "9") (pinfunction "-IN_9") (pintype "input"))
      (node (ref "R12") (pin "2") (pinfunction "2_2") (pintype "passive"))
      (node (ref "R15") (pin "1") (pinfunction "1_1") (pintype "passive"))
      (node (ref "R16") (pin "1") (pinfunction "1_1") (pintype "passive"))
    )
    (net (code "69") (name "Net-(IC6D--IN)") (class "Default")
      (node (ref "C14") (pin "1") (pinfunction "1_1") (pintype "passive"))
      (node (ref "IC6") (pin "13") (pinfunction "-IN_13") (pintype "input"))
      (node (ref "R11") (pin "2") (pinfunction "2_2") (pintype "passive"))
      (node (ref "R13") (pin "1") (pinfunction "1_1") (pintype "passive"))
      (node (ref "R14") (pin "1") (pinfunction "1_1") (pintype "passive"))
    )
    (net (code "70") (name "Net-(IC7A--IN)") (class "Default")
      (node (ref "C30") (pin "1") (pinfunction "1_1") (pintype "passive"))
      (node (ref "IC7") (pin "2") (pinfunction "-IN_2") (pintype "input"))
      (node (ref "R40") (pin "1") (pinfunction "1_1") (pintype "passive"))
      (node (ref "R41") (pin "1") (pinfunction "1_1") (pintype "passive"))
      (node (ref "R46") (pin "2") (pinfunction "2_2") (pintype "passive"))
    )
    (net (code "71") (name "Net-(IC7B--IN)") (class "Default")
      (node (ref "C28") (pin "1") (pinfunction "1_1") (pintype "passive"))
      (node (ref "IC7") (pin "6") (pinfunction "-IN_6") (pintype "input"))
      (node (ref "R29") (pin "2") (pinfunction "2_2") (pintype "passive"))
      (node (ref "R42") (pin "1") (pinfunction "1_1") (pintype "passive"))
      (node (ref "R43") (pin "1") (pinfunction "1_1") (pintype "passive"))
    )
    (net (code "72") (name "Net-(IC7C--IN)") (class "Default")
      (node (ref "C20") (pin "1") (pinfunction "1_1") (pintype "passive"))
      (node (ref "IC7") (pin "9") (pinfunction "-IN_9") (pintype "input"))
      (node (ref "R18") (pin "2") (pinfunction "2_2") (pintype "passive"))
      (node (ref "R21") (pin "1") (pinfunction "1_1") (pintype "passive"))
      (node (ref "R22") (pin "1") (pinfunction "1_1") (pintype "passive"))
    )
    (net (code "73") (name "Net-(IC7D--IN)") (class "Default")
      (node (ref "C19") (pin "1") (pinfunction "1_1") (pintype "passive"))
      (node (ref "IC7") (pin "13") (pinfunction "-IN_13") (pintype "input"))
      (node (ref "R17") (pin "2") (pinfunction "2_2") (pintype "passive"))
      (node (ref "R19") (pin "1") (pinfunction "1_1") (pintype "passive"))
      (node (ref "R20") (pin "1") (pinfunction "1_1") (pintype "passive"))
    )
    (net (code "74") (name "Net-(IC8A-X0)") (class "Default")
      (node (ref "IC8") (pin "13") (pinfunction "X0_13") (pintype "bidirectional"))
      (node (ref "R79") (pin "P$2") (pinfunction "S_P$2") (pintype "passive"))
    )
    (net (code "75") (name "Net-(IC8A-X1)") (class "Default")
      (node (ref "IC8") (pin "14") (pinfunction "X1_14") (pintype "bidirectional"))
      (node (ref "R80") (pin "P$2") (pinfunction "S_P$2") (pintype "passive"))
    )
    (net (code "76") (name "Net-(IC8A-X2)") (class "Default")
      (node (ref "IC8") (pin "15") (pinfunction "X2_15") (pintype "bidirectional"))
      (node (ref "R81") (pin "P$2") (pinfunction "S_P$2") (pintype "passive"))
    )
    (net (code "77") (name "Net-(IC8A-X3)") (class "Default")
      (node (ref "IC8") (pin "12") (pinfunction "X3_12") (pintype "bidirectional"))
      (node (ref "R78") (pin "P$2") (pinfunction "S_P$2") (pintype "passive"))
    )
    (net (code "78") (name "Net-(IC9A--IN)") (class "Default")
      (node (ref "C24") (pin "1") (pinfunction "1_1") (pintype "passive"))
      (node (ref "IC9") (pin "2") (pinfunction "-IN_2") (pintype "input"))
      (node (ref "R27") (pin "2") (pinfunction "2_2") (pintype "passive"))
      (node (ref "R36") (pin "1") (pinfunction "1_1") (pintype "passive"))
      (node (ref "R37") (pin "1") (pinfunction "1_1") (pintype "passive"))
    )
    (net (code "79") (name "Net-(IC9B--IN)") (class "Default")
      (node (ref "C25") (pin "1") (pinfunction "1_1") (pintype "passive"))
      (node (ref "IC9") (pin "6") (pinfunction "-IN_6") (pintype "input"))
      (node (ref "R28") (pin "2") (pinfunction "2_2") (pintype "passive"))
      (node (ref "R38") (pin "1") (pinfunction "1_1") (pintype "passive"))
      (node (ref "R39") (pin "1") (pinfunction "1_1") (pintype "passive"))
    )
    (net (code "80") (name "Net-(IC10-PA8{slash}USART1_CK{slash}TIM1_CH1{slash}MCO)") (class "Default")
      (node (ref "IC10") (pin "41") (pinfunction "PA8/USART1_CK/TIM1_CH1/MCO_41") (pintype "bidirectional"))
      (node (ref "R47") (pin "1") (pinfunction "1_1") (pintype "passive"))
    )
    (net (code "81") (name "Net-(IC10-PA11{slash}USART1_CTS{slash}CANRX{slash}USBDM{slash}TIM1_CH4)") (class "Default")
      (node (ref "IC10") (pin "44") (pinfunction "PA11/USART1_CTS/CANRX/USBDM/TIM1_CH4_44") (pintype "bidirectional"))
      (node (ref "R44") (pin "1") (pinfunction "1_1") (pintype "passive"))
    )
    (net (code "82") (name "Net-(IC10-PD0{slash}OSC_IN)") (class "Default")
      (node (ref "C12") (pin "2") (pinfunction "2_2") (pintype "passive"))
      (node (ref "IC10") (pin "5") (pinfunction "PD0/OSC_IN_5") (pintype "bidirectional"))
      (node (ref "Q1") (pin "2") (pinfunction "2_2") (pintype "passive"))
    )
    (net (code "83") (name "Net-(IC10-PD1{slash}OSC_OUT)") (class "Default")
      (node (ref "C11") (pin "2") (pinfunction "2_2") (pintype "passive"))
      (node (ref "IC10") (pin "6") (pinfunction "PD1/OSC_OUT_6") (pintype "bidirectional"))
      (node (ref "Q1") (pin "1") (pinfunction "1_1") (pintype "passive"))
    )
    (net (code "84") (name "Net-(IC10-VCAP_1)") (class "Default")
      (node (ref "C31") (pin "1") (pinfunction "1_1") (pintype "passive"))
      (node (ref "IC10") (pin "31") (pinfunction "VCAP_1_31") (pintype "power_in"))
    )
    (net (code "85") (name "Net-(IC10-VCAP_2)") (class "Default")
      (node (ref "C35") (pin "1") (pinfunction "1_1") (pintype "passive"))
      (node (ref "IC10") (pin "47") (pinfunction "VCAP_2_47") (pintype "power_in"))
    )
    (net (code "86") (name "Net-(IC11A-X0)") (class "Default")
      (node (ref "IC11") (pin "13") (pinfunction "X0_13") (pintype "bidirectional"))
      (node (ref "R65") (pin "P$2") (pinfunction "S_P$2") (pintype "passive"))
    )
    (net (code "87") (name "Net-(IC11A-X1)") (class "Default")
      (node (ref "IC11") (pin "14") (pinfunction "X1_14") (pintype "bidirectional"))
      (node (ref "R76") (pin "P$2") (pinfunction "S_P$2") (pintype "passive"))
    )
    (net (code "88") (name "Net-(IC11A-X2)") (class "Default")
      (node (ref "IC11") (pin "15") (pinfunction "X2_15") (pintype "bidirectional"))
      (node (ref "R77") (pin "P$2") (pinfunction "S_P$2") (pintype "passive"))
    )
    (net (code "89") (name "Net-(IC11A-X4)") (class "Default")
      (node (ref "IC11") (pin "1") (pinfunction "X4_1") (pintype "bidirectional"))
      (node (ref "R64") (pin "P$2") (pinfunction "S_P$2") (pintype "passive"))
    )
    (net (code "90") (name "Net-(IC11A-X5)") (class "Default")
      (node (ref "IC11") (pin "5") (pinfunction "X5_5") (pintype "bidirectional"))
      (node (ref "R61") (pin "P$2") (pinfunction "S_P$2") (pintype "passive"))
    )
    (net (code "91") (name "Net-(IC11A-X6)") (class "Default")
      (node (ref "IC11") (pin "2") (pinfunction "X6_2") (pintype "bidirectional"))
      (node (ref "R63") (pin "P$2") (pinfunction "S_P$2") (pintype "passive"))
    )
    (net (code "92") (name "Net-(IC11A-X7)") (class "Default")
      (node (ref "IC11") (pin "4") (pinfunction "X7_4") (pintype "bidirectional"))
      (node (ref "R62") (pin "P$2") (pinfunction "S_P$2") (pintype "passive"))
    )
    (net (code "93") (name "Net-(IC12-VMID)") (class "Default")
      (node (ref "C47") (pin "1") (pinfunction "1_1") (pintype "passive"))
      (node (ref "C52") (pin "+") (pinfunction "+_+") (pintype "passive"))
      (node (ref "IC12") (pin "16") (pinfunction "VMID_16") (pintype "bidirectional"))
    )
    (net (code "94") (name "Net-(IC13A--IN)") (class "Default")
      (node (ref "IC13") (pin "1") (pinfunction "OUT_1") (pintype "output"))
      (node (ref "IC13") (pin "2") (pinfunction "-IN_2") (pintype "input"))
    )
    (net (code "95") (name "Net-(IC13B--IN)") (class "Default")
      (node (ref "C50") (pin "1") (pinfunction "1_1") (pintype "passive"))
      (node (ref "IC13") (pin "6") (pinfunction "-IN_6") (pintype "input"))
      (node (ref "R70") (pin "1") (pinfunction "1_1") (pintype "passive"))
      (node (ref "R71") (pin "1") (pinfunction "1_1") (pintype "passive"))
      (node (ref "R73") (pin "2") (pinfunction "2_2") (pintype "passive"))
    )
    (net (code "96") (name "Net-(IC13C--IN)") (class "Default")
      (node (ref "C42") (pin "1") (pinfunction "1_1") (pintype "passive"))
      (node (ref "IC13") (pin "9") (pinfunction "-IN_9") (pintype "input"))
      (node (ref "R49") (pin "2") (pinfunction "2_2") (pintype "passive"))
      (node (ref "R56") (pin "1") (pinfunction "1_1") (pintype "passive"))
      (node (ref "R57") (pin "1") (pinfunction "1_1") (pintype "passive"))
    )
    (net (code "97") (name "Net-(IC13D--IN)") (class "Default")
      (node (ref "C41") (pin "1") (pinfunction "1_1") (pintype "passive"))
      (node (ref "IC13") (pin "13") (pinfunction "-IN_13") (pintype "input"))
      (node (ref "R48") (pin "2") (pinfunction "2_2") (pintype "passive"))
      (node (ref "R54") (pin "1") (pinfunction "1_1") (pintype "passive"))
      (node (ref "R55") (pin "1") (pinfunction "1_1") (pintype "passive"))
    )
    (net (code "98") (name "Net-(IC14A--IN)") (class "Default")
      (node (ref "C49") (pin "1") (pinfunction "1_1") (pintype "passive"))
      (node (ref "IC14") (pin "2") (pinfunction "-IN_2") (pintype "input"))
      (node (ref "R68") (pin "1") (pinfunction "1_1") (pintype "passive"))
      (node (ref "R72") (pin "2") (pinfunction "2_2") (pintype "passive"))
    )
    (net (code "99") (name "Net-(IC14A-OUT)") (class "Default")
      (node (ref "C49") (pin "2") (pinfunction "2_2") (pintype "passive"))
      (node (ref "IC14") (pin "1") (pinfunction "OUT_1") (pintype "output"))
      (node (ref "R72") (pin "1") (pinfunction "1_1") (pintype "passive"))
      (node (ref "R89") (pin "2") (pinfunction "2_2") (pintype "passive"))
    )
    (net (code "100") (name "Net-(IC14B--IN)") (class "Default")
      (node (ref "C43") (pin "1") (pinfunction "1_1") (pintype "passive"))
      (node (ref "IC14") (pin "6") (pinfunction "-IN_6") (pintype "input"))
      (node (ref "R51") (pin "2") (pinfunction "2_2") (pintype "passive"))
      (node (ref "R58") (pin "1") (pinfunction "1_1") (pintype "passive"))
    )
    (net (code "101") (name "Net-(IC14B-OUT)") (class "Default")
      (node (ref "C43") (pin "2") (pinfunction "2_2") (pintype "passive"))
      (node (ref "IC14") (pin "7") (pinfunction "OUT_7") (pintype "output"))
      (node (ref "R51") (pin "1") (pinfunction "1_1") (pintype "passive"))
      (node (ref "R88") (pin "2") (pinfunction "2_2") (pintype "passive"))
    )
    (net (code "102") (name "Net-(J1-3)") (class "Default")
      (node (ref "J1") (pin "P3") (pinfunction "3_P3") (pintype "passive"))
      (node (ref "R36") (pin "2") (pinfunction "2_2") (pintype "passive"))
    )
    (net (code "103") (name "Net-(J2-3)") (class "Default")
      (node (ref "J2") (pin "P3") (pinfunction "3_P3") (pintype "passive"))
      (node (ref "R39") (pin "2") (pinfunction "2_2") (pintype "passive"))
    )
    (net (code "104") (name "Net-(J3-3)") (class "Default")
      (node (ref "J3") (pin "P3") (pinfunction "3_P3") (pintype "passive"))
      (node (ref "R67") (pin "1") (pinfunction "1_1") (pintype "passive"))
    )
    (net (code "105") (name "Net-(J4-3)") (class "Default")
      (node (ref "J4") (pin "P3") (pinfunction "3_P3") (pintype "passive"))
      (node (ref "R30") (pin "2") (pinfunction "2_2") (pintype "passive"))
    )
    (net (code "106") (name "Net-(J5-3)") (class "Default")
      (node (ref "J5") (pin "P3") (pinfunction "3_P3") (pintype "passive"))
      (node (ref "R75") (pin "2") (pinfunction "2_2") (pintype "passive"))
    )
    (net (code "107") (name "Net-(J6-3)") (class "Default")
      (node (ref "J6") (pin "P3") (pinfunction "3_P3") (pintype "passive"))
      (node (ref "R86") (pin "2") (pinfunction "2_2") (pintype "passive"))
    )
    (net (code "108") (name "Net-(J7-3)") (class "Default")
      (node (ref "J7") (pin "P3") (pinfunction "3_P3") (pintype "passive"))
      (node (ref "R88") (pin "1") (pinfunction "1_1") (pintype "passive"))
    )
    (net (code "109") (name "Net-(J8-3)") (class "Default")
      (node (ref "J8") (pin "P3") (pinfunction "3_P3") (pintype "passive"))
      (node (ref "R89") (pin "1") (pinfunction "1_1") (pintype "passive"))
    )
    (net (code "110") (name "Net-(J9-3)") (class "Default")
      (node (ref "J9") (pin "P3") (pinfunction "3_P3") (pintype "passive"))
      (node (ref "R13") (pin "2") (pinfunction "2_2") (pintype "passive"))
    )
    (net (code "111") (name "Net-(J10-3)") (class "Default")
      (node (ref "J10") (pin "P3") (pinfunction "3_P3") (pintype "passive"))
      (node (ref "R16") (pin "2") (pinfunction "2_2") (pintype "passive"))
    )
    (net (code "112") (name "Net-(J11-3)") (class "Default")
      (node (ref "J11") (pin "P3") (pinfunction "3_P3") (pintype "passive"))
      (node (ref "R33") (pin "2") (pinfunction "2_2") (pintype "passive"))
    )
    (net (code "113") (name "Net-(J12-3)") (class "Default")
      (node (ref "J12") (pin "P3") (pinfunction "3_P3") (pintype "passive"))
      (node (ref "R40") (pin "2") (pinfunction "2_2") (pintype "passive"))
    )
    (net (code "114") (name "Net-(J13-3)") (class "Default")
      (node (ref "J13") (pin "P3") (pinfunction "3_P3") (pintype "passive"))
      (node (ref "R19") (pin "2") (pinfunction "2_2") (pintype "passive"))
    )
    (net (code "115") (name "Net-(J14-3)") (class "Default")
      (node (ref "J14") (pin "P3") (pinfunction "3_P3") (pintype "passive"))
      (node (ref "R22") (pin "2") (pinfunction "2_2") (pintype "passive"))
    )
    (net (code "116") (name "Net-(J15-3)") (class "Default")
      (node (ref "J15") (pin "P3") (pinfunction "3_P3") (pintype "passive"))
      (node (ref "R43") (pin "2") (pinfunction "2_2") (pintype "passive"))
    )
    (net (code "117") (name "Net-(J16-3)") (class "Default")
      (node (ref "J16") (pin "P3") (pinfunction "3_P3") (pintype "passive"))
      (node (ref "R54") (pin "2") (pinfunction "2_2") (pintype "passive"))
    )
    (net (code "118") (name "Net-(J17-3)") (class "Default")
      (node (ref "J17") (pin "P3") (pinfunction "3_P3") (pintype "passive"))
      (node (ref "R57") (pin "2") (pinfunction "2_2") (pintype "passive"))
    )
    (net (code "119") (name "Net-(J18-3)") (class "Default")
      (node (ref "J18") (pin "P3") (pinfunction "3_P3") (pintype "passive"))
      (node (ref "R71") (pin "2") (pinfunction "2_2") (pintype "passive"))
    )
    (net (code "120") (name "Net-(LED1-PadA)") (class "Default")
      (node (ref "LED1") (pin "A") (pinfunction "A_A") (pintype "passive"))
      (node (ref "R47") (pin "2") (pinfunction "2_2") (pintype "passive"))
    )
    (net (code "121") (name "Net-(LED2-PadA)") (class "Default")
      (node (ref "LED2") (pin "A") (pinfunction "A_A") (pintype "passive"))
      (node (ref "R44") (pin "2") (pinfunction "2_2") (pintype "passive"))
    )
    (net (code "122") (name "Net-(Q2-PadB)") (class "Default")
      (node (ref "Q2") (pin "B") (pinfunction "B_B") (pintype "passive"))
      (node (ref "R67") (pin "2") (pinfunction "2_2") (pintype "passive"))
    )
    (net (code "123") (name "Net-(R10-Pad2)") (class "Default")
      (node (ref "R10") (pin "2") (pinfunction "2_2") (pintype "passive"))
      (node (ref "SW1") (pin "L1") (pinfunction "L1_L1") (pintype "passive"))
    )
    (net (code "124") (name "RESET") (class "Default")
      (node (ref "IC10") (pin "7") (pinfunction "NRST_7") (pintype "bidirectional"))
      (node (ref "JP1") (pin "10") (pinfunction "10_10") (pintype "passive"))
      (node (ref "R45") (pin "1") (pinfunction "1_1") (pintype "passive"))
      (node (ref "SW2") (pin "B") (pinfunction "S_B") (pintype "passive"))
      (node (ref "SW2") (pin "B'") (pinfunction "S1_B'") (pintype "passive"))
    )
    (net (code "125") (name "RIN") (class "Default")
      (node (ref "C55") (pin "+") (pinfunction "+_+") (pintype "passive"))
      (node (ref "IC12") (pin "19") (pinfunction "RLINEIN_19") (pintype "bidirectional"))
    )
    (net (code "126") (name "ROUT") (class "Default")
      (node (ref "C53") (pin "+") (pinfunction "+_+") (pintype "passive"))
      (node (ref "IC12") (pin "13") (pinfunction "ROUT_13") (pintype "bidirectional"))
    )
    (net (code "127") (name "RX") (class "Default")
      (node (ref "IC10") (pin "43") (pinfunction "PA10/USART1_RX/TIM1_CH3_43") (pintype "bidirectional"))
      (node (ref "JP2") (pin "4") (pinfunction "4_4") (pintype "passive"))
    )
    (net (code "128") (name "SW_GATE") (class "Default")
      (node (ref "IC10") (pin "9") (pinfunction "PC1/ADC11_9") (pintype "bidirectional"))
      (node (ref "SW1") (pin "P2") (pinfunction "A2_P2") (pintype "passive"))
      (node (ref "SW1") (pin "P5") (pinfunction "B2_P5") (pintype "passive"))
    )
    (net (code "129") (name "TX") (class "Default")
      (node (ref "IC10") (pin "42") (pinfunction "PA9/USART1_TX/TIM1_CH2_42") (pintype "bidirectional"))
      (node (ref "JP2") (pin "5") (pinfunction "5_5") (pintype "passive"))
    )
    (net (code "130") (name "VBAT") (class "Default")
      (node (ref "IC10") (pin "1") (pinfunction "VBAT_1") (pintype "power_in"))
    )
    (net (code "131") (name "VCC") (class "Default")
      (node (ref "C3") (pin "+") (pinfunction "+_+") (pintype "passive"))
      (node (ref "C44") (pin "1") (pinfunction "1_1") (pintype "passive"))
      (node (ref "D1") (pin "C") (pinfunction "C_C") (pintype "passive"))
      (node (ref "IC14") (pin "8") (pinfunction "V+_8") (pintype "power_in"))
      (node (ref "L1") (pin "1") (pinfunction "1_1") (pintype "passive"))
      (node (ref "L2") (pin "1") (pinfunction "1_1") (pintype "passive"))
    )
    (net (code "132") (name "VEE") (class "Default")
      (node (ref "C1") (pin "-") (pinfunction "-_-") (pintype "passive"))
      (node (ref "C45") (pin "2") (pinfunction "2_2") (pintype "passive"))
      (node (ref "D2") (pin "A") (pinfunction "A_A") (pintype "passive"))
      (node (ref "IC14") (pin "4") (pinfunction "V-_4") (pintype "power_in"))
      (node (ref "R1") (pin "1") (pinfunction "1_1") (pintype "passive"))
      (node (ref "R2") (pin "1") (pinfunction "1_1") (pintype "passive"))
    )
    (net (code "133") (name "unconnected-(IC10-PA12{slash}USART1_RTS{slash}CANTX{slash}USBDP{slash}TIM1_ETR-Pad45)") (class "Default")
      (node (ref "IC10") (pin "45") (pinfunction "PA12/USART1_RTS/CANTX/USBDP/TIM1_ETR_45") (pintype "bidirectional"))
    )
    (net (code "134") (name "unconnected-(IC10-PB4{slash}NJTRST{slash}SPI3_MISO{slash}SPI1_MISO-Pad56)") (class "Default")
      (node (ref "IC10") (pin "56") (pinfunction "PB4/NJTRST/SPI3_MISO/SPI1_MISO_56") (pintype "bidirectional"))
    )
    (net (code "135") (name "unconnected-(IC10-PB9{slash}SPI2_NSS{slash}I2S2_WS{slash}I2C1_SDA{slash}TIM4_CH4-Pad62)") (class "Default")
      (node (ref "IC10") (pin "62") (pinfunction "PB9/SPI2_NSS/I2S2_WS/I2C1_SDA/TIM4_CH4_62") (pintype "bidirectional"))
    )
    (net (code "136") (name "unconnected-(IC10-PC8-Pad39)") (class "Default")
      (node (ref "IC10") (pin "39") (pinfunction "PC8_39") (pintype "bidirectional"))
    )
    (net (code "137") (name "unconnected-(IC10-PC9{slash}I2S2_CKIN{slash}I2S3_CKIN-Pad40)") (class "Default")
      (node (ref "IC10") (pin "40") (pinfunction "PC9/I2S2_CKIN/I2S3_CKIN_40") (pintype "bidirectional"))
    )
    (net (code "138") (name "unconnected-(IC10-PC10{slash}SPI3_SCK{slash}I2S3_SCK{slash}UART4_TX-Pad51)") (class "Default")
      (node (ref "IC10") (pin "51") (pinfunction "PC10/SPI3_SCK/I2S3_SCK/UART4_TX_51") (pintype "bidirectional"))
    )
    (net (code "139") (name "unconnected-(IC10-PC11{slash}UART4_RX{slash}SPI3_MISO{slash}USART3_RX-Pad52)") (class "Default")
      (node (ref "IC10") (pin "52") (pinfunction "PC11/UART4_RX/SPI3_MISO/USART3_RX_52") (pintype "bidirectional"))
    )
    (net (code "140") (name "unconnected-(IC10-PC12{slash}UART5_TX{slash}I2S3_SD{slash}USART3_CK-Pad53)") (class "Default")
      (node (ref "IC10") (pin "53") (pinfunction "PC12/UART5_TX/I2S3_SD/USART3_CK_53") (pintype "bidirectional"))
    )
    (net (code "141") (name "unconnected-(IC10-PD2{slash}TIM3-ETR-Pad54)") (class "Default")
      (node (ref "IC10") (pin "54") (pinfunction "PD2/TIM3-ETR_54") (pintype "bidirectional"))
    )
    (net (code "142") (name "unconnected-(IC12-CLKOUT-Pad2)") (class "Default")
      (node (ref "IC12") (pin "2") (pinfunction "CLKOUT_2") (pintype "bidirectional"))
    )
    (net (code "143") (name "unconnected-(IC12-LHPOUT-Pad9)") (class "Default")
      (node (ref "IC12") (pin "9") (pinfunction "LHPOUT_9") (pintype "bidirectional"))
    )
    (net (code "144") (name "unconnected-(IC12-MICBIAS-Pad17)") (class "Default")
      (node (ref "IC12") (pin "17") (pinfunction "MICBIAS_17") (pintype "bidirectional"))
    )
    (net (code "145") (name "unconnected-(IC12-MICIN-Pad18)") (class "Default")
      (node (ref "IC12") (pin "18") (pinfunction "MICIN_18") (pintype "bidirectional"))
    )
    (net (code "146") (name "unconnected-(IC12-RHPOUT-Pad10)") (class "Default")
      (node (ref "IC12") (pin "10") (pinfunction "RHPOUT_10") (pintype "bidirectional"))
    )
    (net (code "147") (name "unconnected-(IC12-XTO-Pad26)") (class "Default")
      (node (ref "IC12") (pin "26") (pinfunction "XTO_26") (pintype "bidirectional"))
    )
    (net (code "148") (name "unconnected-(J1-2-PadP2)") (class "Default")
      (node (ref "J1") (pin "P2") (pinfunction "2_P2") (pintype "passive"))
    )
    (net (code "149") (name "unconnected-(J2-2-PadP2)") (class "Default")
      (node (ref "J2") (pin "P2") (pinfunction "2_P2") (pintype "passive"))
    )
    (net (code "150") (name "unconnected-(J4-2-PadP2)") (class "Default")
      (node (ref "J4") (pin "P2") (pinfunction "2_P2") (pintype "passive"))
    )
    (net (code "151") (name "unconnected-(J5-2-PadP2)") (class "Default")
      (node (ref "J5") (pin "P2") (pinfunction "2_P2") (pintype "passive"))
    )
    (net (code "152") (name "unconnected-(J6-2-PadP2)") (class "Default")
      (node (ref "J6") (pin "P2") (pinfunction "2_P2") (pintype "passive"))
    )
    (net (code "153") (name "unconnected-(J7-2-PadP2)") (class "Default")
      (node (ref "J7") (pin "P2") (pinfunction "2_P2") (pintype "passive"))
    )
    (net (code "154") (name "unconnected-(J8-2-PadP2)") (class "Default")
      (node (ref "J8") (pin "P2") (pinfunction "2_P2") (pintype "passive"))
    )
    (net (code "155") (name "unconnected-(J9-2-PadP2)") (class "Default")
      (node (ref "J9") (pin "P2") (pinfunction "2_P2") (pintype "passive"))
    )
    (net (code "156") (name "unconnected-(J10-2-PadP2)") (class "Default")
      (node (ref "J10") (pin "P2") (pinfunction "2_P2") (pintype "passive"))
    )
    (net (code "157") (name "unconnected-(J11-2-PadP2)") (class "Default")
      (node (ref "J11") (pin "P2") (pinfunction "2_P2") (pintype "passive"))
    )
    (net (code "158") (name "unconnected-(J12-2-PadP2)") (class "Default")
      (node (ref "J12") (pin "P2") (pinfunction "2_P2") (pintype "passive"))
    )
    (net (code "159") (name "unconnected-(J13-2-PadP2)") (class "Default")
      (node (ref "J13") (pin "P2") (pinfunction "2_P2") (pintype "passive"))
    )
    (net (code "160") (name "unconnected-(J14-2-PadP2)") (class "Default")
      (node (ref "J14") (pin "P2") (pinfunction "2_P2") (pintype "passive"))
    )
    (net (code "161") (name "unconnected-(J15-2-PadP2)") (class "Default")
      (node (ref "J15") (pin "P2") (pinfunction "2_P2") (pintype "passive"))
    )
    (net (code "162") (name "unconnected-(J16-2-PadP2)") (class "Default")
      (node (ref "J16") (pin "P2") (pinfunction "2_P2") (pintype "passive"))
    )
    (net (code "163") (name "unconnected-(J17-2-PadP2)") (class "Default")
      (node (ref "J17") (pin "P2") (pinfunction "2_P2") (pintype "passive"))
    )
    (net (code "164") (name "unconnected-(J18-2-PadP2)") (class "Default")
      (node (ref "J18") (pin "P2") (pinfunction "2_P2") (pintype "passive"))
    )
    (net (code "165") (name "unconnected-(JP1-Pad7)") (class "Default")
      (node (ref "JP1") (pin "7") (pinfunction "7_7") (pintype "passive"))
    )
    (net (code "166") (name "unconnected-(JP2-Pad2)") (class "Default")
      (node (ref "JP2") (pin "2") (pinfunction "2_2") (pintype "passive"))
    )
    (net (code "167") (name "unconnected-(JP2-Pad3)") (class "Default")
      (node (ref "JP2") (pin "3") (pinfunction "3_3") (pintype "passive"))
    )
    (net (code "168") (name "unconnected-(JP2-Pad6)") (class "Default")
      (node (ref "JP2") (pin "6") (pinfunction "6_6") (pintype "passive"))
    )
    (net (code "169") (name "unconnected-(SW1A-A1-PadP1)") (class "Default")
      (node (ref "SW1") (pin "P1") (pinfunction "A1_P1") (pintype "passive"))
    )
    (net (code "170") (name "unconnected-(SW1A-B1-PadP4)") (class "Default")
      (node (ref "SW1") (pin "P4") (pinfunction "B1_P4") (pintype "passive"))
    )
  )
)
